# EVO_Schematic.net
KiCad netlist of a schematic drawn in Altium Designer
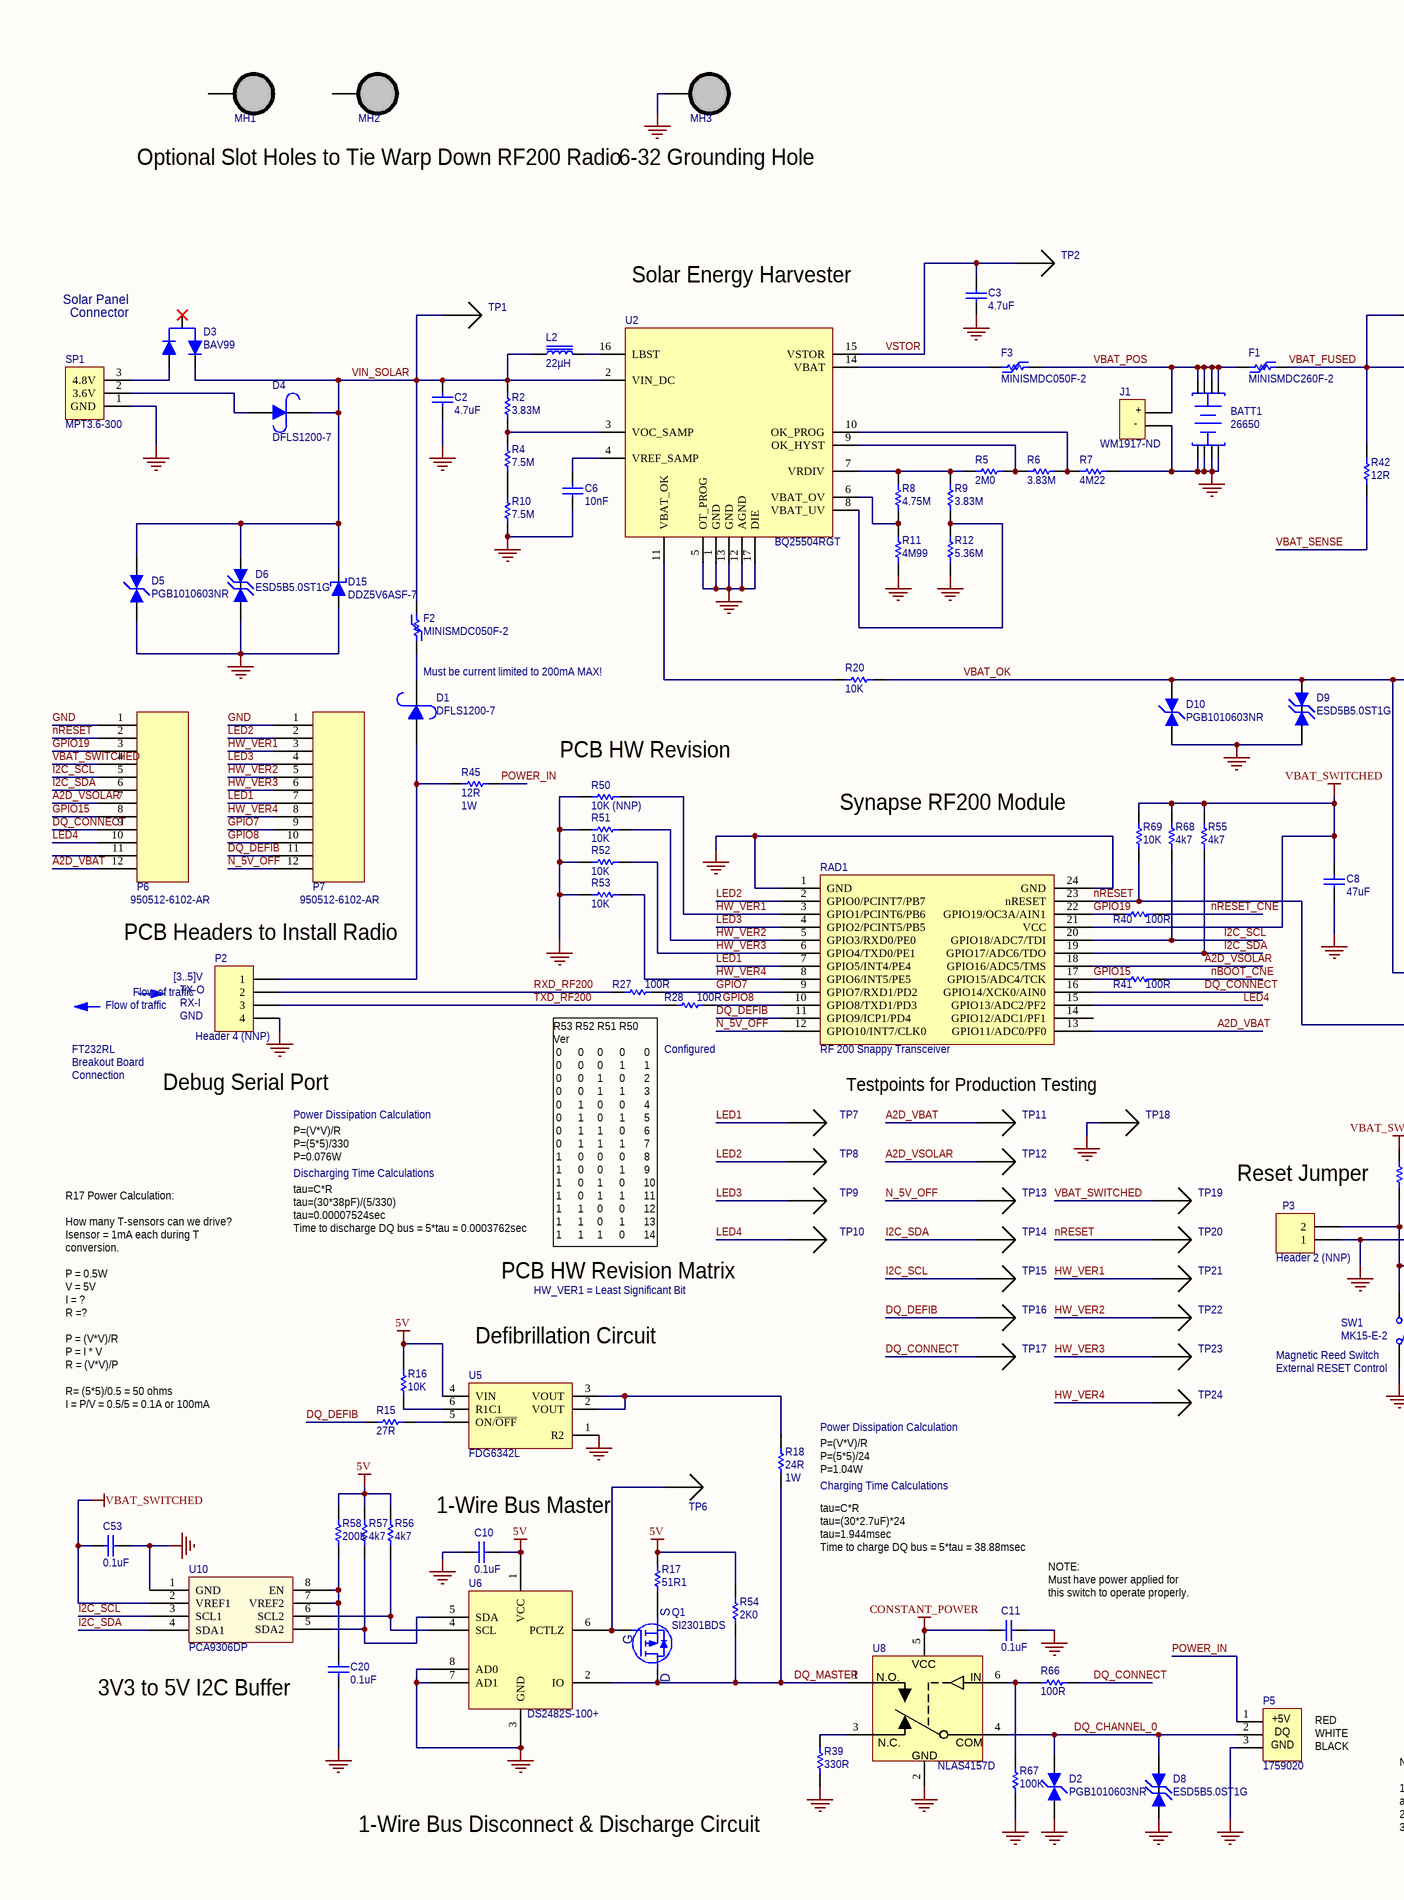
[diagram p0: EVO Schematic.SchDoc, left]
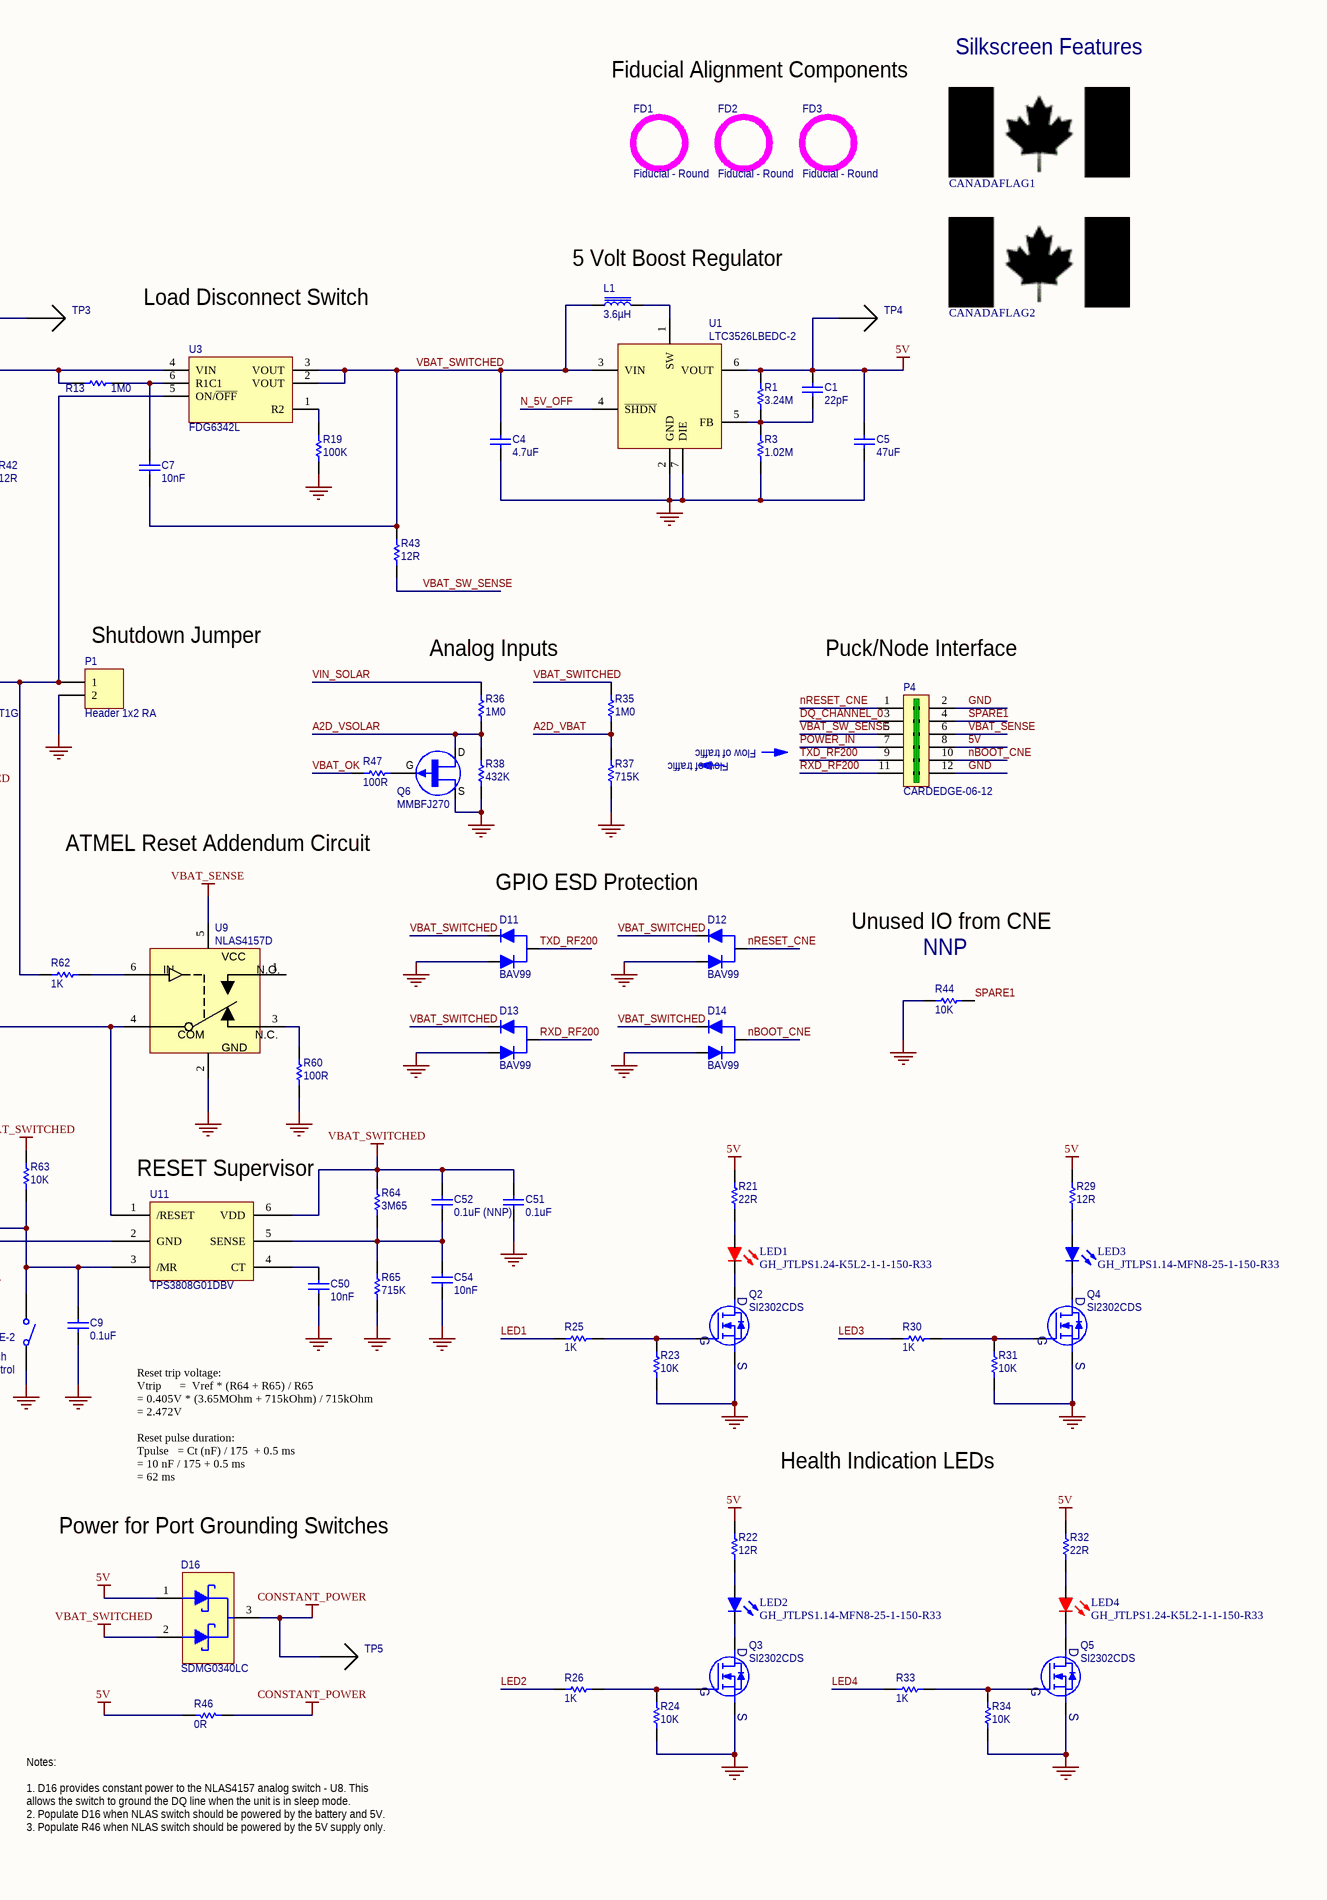
[diagram p1: EVO Schematic.SchDoc, right]

(export (version "E")
  (design (tool "Eeschema 10.0.6"))
  (components
    (comp (ref "BATT1")
      (value "26650")
      (footprint "Battery_26650")
      (description "26650 LiFePO4 3.2V 3300mAh")
      (fields
        (field (name "MANUFACTURER") "TACBattery")
        (field (name "MANUFACTURER PART NUMBER") "26650 3.2V 1500mAh with wire")
      )
      (libsource (lib "Swage") (part "BATT_18650_1"))
    )
    (comp (ref "C1")
      (value "22pF")
      (footprint "RC0805")
      (description "CAP CER 22PF 50V 5% NPO 0805")
      (fields
        (field (name "MANUFACTURER") "Yageo")
        (field (name "MANUFACTURER PART NUMBER") "CC0805JRNPO9BN220")
      )
      (libsource (lib "Swage") (part "CC0805JRNPO9BN220"))
    )
    (comp (ref "C2")
      (value "4.7uF")
      (footprint "RC0805")
      (description "CAP CER 4.7UF 6.3V 10% X5R 0805")
      (fields
        (field (name "MANUFACTURER") "Taiyo Yuden")
        (field (name "MANUFACTURER PART NUMBER") "JMK212BJ475KG-T")
      )
      (libsource (lib "Swage") (part "JMK212BJ475KG-T"))
    )
    (comp (ref "C3")
      (value "4.7uF")
      (footprint "RC0805")
      (description "CAP CER 4.7UF 6.3V 10% X5R 0805")
      (fields
        (field (name "MANUFACTURER") "Taiyo Yuden")
        (field (name "MANUFACTURER PART NUMBER") "JMK212BJ475KG-T")
      )
      (libsource (lib "Swage") (part "JMK212BJ475KG-T"))
    )
    (comp (ref "C4")
      (value "4.7uF")
      (footprint "RC0805")
      (description "CAP CER 4.7UF 6.3V 10% X5R 0805")
      (fields
        (field (name "MANUFACTURER") "Taiyo Yuden")
        (field (name "MANUFACTURER PART NUMBER") "JMK212BJ475KG-T")
      )
      (libsource (lib "Swage") (part "JMK212BJ475KG-T"))
    )
    (comp (ref "C5")
      (value "47uF")
      (footprint "RC1206")
      (description "CAP CER 47UF 10V 20% X5R 1206")
      (fields
        (field (name "MANUFACTURER") "Taiyo Yuden")
        (field (name "MANUFACTURER PART NUMBER") "LMK316BJ476ML-T")
      )
      (libsource (lib "Swage") (part "LMK316BJ476ML-T"))
    )
    (comp (ref "C6")
      (value "10nF")
      (footprint "RC0805")
      (description "CAP CER 10000PF 100V X7R 0805")
      (fields
        (field (name "MANUFACTURER") "TDK Corporation")
        (field (name "MANUFACTURER PART NUMBER") "C2012X7R2A103K")
      )
      (libsource (lib "Swage") (part "C2012X7R2A103K"))
    )
    (comp (ref "C7")
      (value "10nF")
      (footprint "RC0603")
      (description "CAP CER 10000PF 50V 10% X7R 0603")
      (fields
        (field (name "MANUFACTURER") "TDK Corporation")
        (field (name "MANUFACTURER PART NUMBER") "C1608X7R1H103K")
      )
      (libsource (lib "Swage") (part "C1608X7R1H103K"))
    )
    (comp (ref "C8")
      (value "47uF")
      (footprint "RC1206")
      (description "CAP CER 47UF 10V 20% X5R 1206")
      (fields
        (field (name "MANUFACTURER") "Taiyo Yuden")
        (field (name "MANUFACTURER PART NUMBER") "LMK316BJ476ML-T")
      )
      (libsource (lib "Swage") (part "LMK316BJ476ML-T"))
    )
    (comp (ref "C9")
      (value "0.1uF")
      (footprint "RC0603")
      (description "CAP CERM .1UF 10% 16V X7R 0603")
      (fields
        (field (name "MANUFACTURER") "AVX Corporation")
        (field (name "MANUFACTURER PART NUMBER") "0603YC104KAT2A")
      )
      (libsource (lib "Swage") (part "0603YC104KAT2A"))
    )
    (comp (ref "C10")
      (value "0.1uF")
      (footprint "RC0603")
      (description "CAP CERM .1UF 10% 16V X7R 0603")
      (fields (field (name "TOLERANCE") "±10%") (field (name "MANUFACTURER PART NUMBER") "0603YC104KAT2A"))
      (libsource (lib "Swage") (part "0603YC104KAT2A"))
    )
    (comp (ref "C11")
      (value "0.1uF")
      (footprint "RC0603")
      (description "CAP CERM .1UF 10% 16V X7R 0603")
      (fields (field (name "TOLERANCE") "±10%") (field (name "MANUFACTURER PART NUMBER") "0603YC104KAT2A"))
      (libsource (lib "Swage") (part "0603YC104KAT2A"))
    )
    (comp (ref "C20")
      (value "0.1uF")
      (footprint "RC0603")
      (description "CAP CERM .1UF 10% 16V X7R 0603")
      (fields (field (name "TOLERANCE") "±10%") (field (name "MANUFACTURER PART NUMBER") "0603YC104KAT2A"))
      (libsource (lib "Swage") (part "0603YC104KAT2A"))
    )
    (comp (ref "C50")
      (value "10nF")
      (footprint "RC0603")
      (description "CAP CER 10000PF 50V 10% X7R 0603")
      (fields (field (name "TOLERANCE") "±10%") (field (name "MANUFACTURER") "TDK Corporation"))
      (libsource (lib "Swage") (part "C1608X7R1H103K"))
    )
    (comp (ref "C51")
      (value "0.1uF")
      (footprint "RC0603")
      (description "CAP CERM .1UF 10% 16V X7R 0603")
      (fields (field (name "TOLERANCE") "±10%") (field (name "MANUFACTURER PART NUMBER") "0603YC104KAT2A"))
      (libsource (lib "Swage") (part "0603YC104KAT2A"))
    )
    (comp (ref "C52")
      (value "0.1uF (NNP)")
      (footprint "RC0603")
      (description "CAP CERM .1UF 10% 16V X7R 0603")
      (fields (field (name "TOLERANCE") "±10%") (field (name "MANUFACTURER PART NUMBER") "0603YC104KAT2A"))
      (libsource (lib "Swage") (part "0603YC104KAT2A"))
    )
    (comp (ref "C53")
      (value "0.1uF")
      (footprint "RC0603")
      (description "CAP CERM .1UF 10% 16V X7R 0603")
      (fields (field (name "TOLERANCE") "±10%") (field (name "MANUFACTURER PART NUMBER") "0603YC104KAT2A"))
      (libsource (lib "Swage") (part "0603YC104KAT2A"))
    )
    (comp (ref "C54")
      (value "10nF")
      (footprint "RC0603")
      (description "CAP CER 10000PF 50V 10% X7R 0603")
      (fields (field (name "TOLERANCE") "±10%") (field (name "MANUFACTURER") "TDK Corporation"))
      (libsource (lib "Swage") (part "C1608X7R1H103K"))
    )
    (comp (ref "CANADAFLAG1")
      (value "Canada Flag")
      (footprint "CanadaFlag500x250")
      (libsource (lib "Swage") (part "CanadaFlag"))
    )
    (comp (ref "CANADAFLAG2")
      (value "Canada Flag")
      (footprint "CanadaFlag500x250")
      (libsource (lib "Swage") (part "CanadaFlag"))
    )
    (comp (ref "D1")
      (value "DFLS1200-7")
      (footprint "POWERDI-123")
      (description "DIODE SCHOTTKY 1A 200V PWRDI 123")
      (fields (field (name "MANUFACTURER") "Diodes Inc"))
      (libsource (lib "Swage") (part "DFLS1200-7"))
    )
    (comp (ref "D2")
      (value "PGB1010603NR")
      (footprint "RC0603")
      (description "SUPPRESSOR ESD 24VDC 0603 SMD")
      (fields (field (name "MANUFACTURER") "Littelfuse Inc"))
      (libsource (lib "Swage") (part "PGB1010603NR"))
    )
    (comp (ref "D3")
      (value "BAV99")
      (footprint "SOT23")
      (description "DIODE SW DUAL 75V 350MW SOT23-3")
      (fields
        (field (name "MANUFACTURER") "Diodes Inc")
        (field (name "MANUFACTURER PART NUMBER") "BAV99-7-F")
      )
      (libsource (lib "Swage") (part "BAV99-7-F"))
    )
    (comp (ref "D4")
      (value "DFLS1200-7")
      (footprint "POWERDI-123")
      (description "DIODE SCHOTTKY 1A 200V PWRDI 123")
      (fields (field (name "MANUFACTURER") "Diodes Inc"))
      (libsource (lib "Swage") (part "DFLS1200-7"))
    )
    (comp (ref "D5")
      (value "PGB1010603NR")
      (footprint "RC0603")
      (description "SUPPRESSOR ESD 24VDC 0603 SMD")
      (fields (field (name "MANUFACTURER") "Littelfuse Inc"))
      (libsource (lib "Swage") (part "PGB1010603NR"))
    )
    (comp (ref "D6")
      (value "ESD5B5.0ST1G")
      (footprint "SOD-523")
      (description "TVS BIDIRECT 50W SOD523")
      (fields (field (name "MANUFACTURER") "ON Semiconductor"))
      (libsource (lib "Swage") (part "ESD5B5.0ST1G"))
    )
    (comp (ref "D8")
      (value "ESD5B5.0ST1G")
      (footprint "SOD-523")
      (description "TVS BIDIRECT 50W SOD523")
      (fields (field (name "MANUFACTURER") "ON Semiconductor"))
      (libsource (lib "Swage") (part "ESD5B5.0ST1G"))
    )
    (comp (ref "D9")
      (value "ESD5B5.0ST1G")
      (footprint "SOD-523")
      (description "TVS BIDIRECT 50W SOD523")
      (fields (field (name "MANUFACTURER") "ON Semiconductor"))
      (libsource (lib "Swage") (part "ESD5B5.0ST1G"))
    )
    (comp (ref "D10")
      (value "PGB1010603NR")
      (footprint "RC0603")
      (description "SUPPRESSOR ESD 24VDC 0603 SMD")
      (fields (field (name "MANUFACTURER") "Littelfuse Inc"))
      (libsource (lib "Swage") (part "PGB1010603NR"))
    )
    (comp (ref "D11")
      (value "BAV99")
      (footprint "SOT23")
      (description "DIODE SW DUAL 75V 350MW SOT23-3")
      (fields
        (field (name "MANUFACTURER") "Diodes Inc")
        (field (name "MANUFACTURER PART NUMBER") "BAV99-7-F")
      )
      (libsource (lib "Swage") (part "BAV99-7-F"))
    )
    (comp (ref "D12")
      (value "BAV99")
      (footprint "SOT23")
      (description "DIODE SW DUAL 75V 350MW SOT23-3")
      (fields
        (field (name "MANUFACTURER") "Diodes Inc")
        (field (name "MANUFACTURER PART NUMBER") "BAV99-7-F")
      )
      (libsource (lib "Swage") (part "BAV99-7-F"))
    )
    (comp (ref "D13")
      (value "BAV99")
      (footprint "SOT23")
      (description "DIODE SW DUAL 75V 350MW SOT23-3")
      (fields
        (field (name "MANUFACTURER") "Diodes Inc")
        (field (name "MANUFACTURER PART NUMBER") "BAV99-7-F")
      )
      (libsource (lib "Swage") (part "BAV99-7-F"))
    )
    (comp (ref "D14")
      (value "BAV99")
      (footprint "SOT23")
      (description "DIODE SW DUAL 75V 350MW SOT23-3")
      (fields
        (field (name "MANUFACTURER") "Diodes Inc")
        (field (name "MANUFACTURER PART NUMBER") "BAV99-7-F")
      )
      (libsource (lib "Swage") (part "BAV99-7-F"))
    )
    (comp (ref "D15")
      (value "DDZ5V6ASF-7")
      (footprint "SOD323F")
      (description "DIODE ZENER 5.42V 500MW SOD323F")
      (fields (field (name "MANUFACTURER") "Diodes Inc") (field (name "TOLERANCE") "±2%"))
      (libsource (lib "Swage") (part "DDZ5V6ASF-7"))
    )
    (comp (ref "D16")
      (value "SDMG0340LC")
      (footprint "SOT-323")
      (description "DIODE SCHOTTKY 40V 30MA SOT323")
      (fields
        (field (name "MANUFACTURER") "Diodes Inc")
        (field (name "MANUFACTURER PART NUMBER") "SDMG0340LC-7-F")
      )
      (libsource (lib "Swage") (part "SDMG0340LC-7-F"))
    )
    (comp (ref "F1")
      (value "MINISMDC260F-2")
      (footprint "MINISMDC260F")
      (description "POLYSWITCH 2.6A RESET FUSE SMD")
      (fields (field (name "MANUFACTURER") "TE Connectivity"))
      (libsource (lib "Swage") (part "MINISMDC260F-2"))
    )
    (comp (ref "F2")
      (value "MINISMDC050F-2")
      (footprint "MINISMD050")
      (description "POLYSWITCH .50A RESET FUSE SMD")
      (fields (field (name "MANUFACTURER") "TE Connectivity"))
      (libsource (lib "Swage") (part "MINISMDC050F-2"))
    )
    (comp (ref "F3")
      (value "MINISMDC050F-2")
      (footprint "MINISMD050")
      (description "POLYSWITCH .50A RESET FUSE SMD")
      (fields (field (name "MANUFACTURER") "TE Connectivity"))
      (libsource (lib "Swage") (part "MINISMDC050F-2"))
    )
    (comp (ref "FD1")
      (value "Fiducial - Round")
      (footprint "FIDUCIAL ROUND SMALL")
      (description "Fiducial Round")
      (libsource (lib "StormaxV13") (part "Fiducial"))
    )
    (comp (ref "FD2")
      (value "Fiducial - Round")
      (footprint "FIDUCIAL ROUND SMALL")
      (description "Fiducial Round")
      (libsource (lib "StormaxV13") (part "Fiducial"))
    )
    (comp (ref "FD3")
      (value "Fiducial - Round")
      (footprint "FIDUCIAL ROUND SMALL")
      (description "Fiducial Round")
      (libsource (lib "StormaxV13") (part "Fiducial"))
    )
    (comp (ref "J1")
      (value "CONN")
      (footprint "BATTERYCONNECTOR")
      (description "CONN HEADER 2POS 3MM VERT GOLD")
      (fields
        (field (name "MANUFACTURER") "Molex Inc")
        (field (name "MANUFACTURER PART NUMBER") "436500216")
        (field (name "SUPPLIER PART NUMBER 1") "WM1917-ND")
      )
      (libsource (lib "Swage") (part "436500216"))
    )
    (comp (ref "L1")
      (value "3.6µH")
      (footprint "IND-WURTH")
      (description "INDUCTOR POWER 3.6UH 1.38A SMD")
      (fields
        (field (name "MANUFACTURER") "Wurth Electronics Inc")
        (field (name "MANUFACTURER PART NUMBER") "744031003")
      )
      (libsource (lib "Swage") (part "744031003"))
    )
    (comp (ref "L2")
      (value "22µH")
      (footprint "IND-SRR0604")
      (description "INDUCTOR PWR 22UH 20% SHIELD SMD")
      (fields
        (field (name "MANUFACTURER") "Bourns Inc.")
        (field (name "MANUFACTURER PART NUMBER") "SRR0604-220ML")
      )
      (libsource (lib "Swage") (part "SRR0604-220ML"))
    )
    (comp (ref "LED1")
      (value "GH_JTLPS1.24-K5L2-1-1-150-R33")
      (footprint "GHJTLPS124K5L211150R33")
      (description "LED")
      (fields (field (name "MANUFACTURER_PART_NUMBER") "GH JTLPS1.24-K5L2-1-1-150-R33"))
      (libsource (lib "Swage") (part "GH_JTLPS1.24-K5L2-1-1-150-R33"))
    )
    (comp (ref "LED2")
      (value "GH_JTLPS1.14-MFN8-25-1-150-R33")
      (footprint "GHJTLPS124K5L211150R33")
      (description "LED")
      (fields (field (name "MANUFACTURER_PART_NUMBER") "GH JTLPS1.24-K5L2-1-1-150-R33"))
      (libsource (lib "Swage") (part "GH_JTLPS1.14-MFN8-25-1-150-R33"))
    )
    (comp (ref "LED3")
      (value "GH_JTLPS1.14-MFN8-25-1-150-R33")
      (footprint "GHJTLPS124K5L211150R33")
      (description "LED")
      (fields (field (name "MANUFACTURER_PART_NUMBER") "GH JTLPS1.24-K5L2-1-1-150-R33"))
      (libsource (lib "Swage") (part "GH_JTLPS1.14-MFN8-25-1-150-R33"))
    )
    (comp (ref "LED4")
      (value "GH_JTLPS1.24-K5L2-1-1-150-R33")
      (footprint "GHJTLPS124K5L211150R33")
      (description "LED")
      (fields (field (name "MANUFACTURER_PART_NUMBER") "GH JTLPS1.24-K5L2-1-1-150-R33"))
      (libsource (lib "Swage") (part "GH_JTLPS1.24-K5L2-1-1-150-R33"))
    )
    (comp (ref "MH1")
      (value "MountingHole")
      (footprint "MountingHole")
      (description "PCB Mounting Hole, 0.150\" hole, 0.270\" Keepout")
      (libsource (lib "Swage") (part "MountingHole"))
    )
    (comp (ref "MH2")
      (value "MountingHole")
      (footprint "MountingHole")
      (description "PCB Mounting Hole, 0.150\" hole, 0.270\" Keepout")
      (libsource (lib "Swage") (part "MountingHole"))
    )
    (comp (ref "MH3")
      (value "MountingHole")
      (footprint "MountingHole")
      (description "PCB Mounting Hole, 0.150\" hole, 0.270\" Keepout")
      (libsource (lib "Swage") (part "MountingHole"))
    )
    (comp (ref "P1")
      (value "Header 1x2 RA")
      (footprint "HDR1X2")
      (description "SIL HORIZ PC TAIL PIN HEADER")
      (fields
        (field (name "MANUFACTURER") "Harwin Inc")
        (field (name "MANUFACTURER PART NUMBER") "M20-9960245")
      )
      (libsource (lib "Swage") (part "M20-9960245"))
    )
    (comp (ref "P2")
      (value "Header 4 (NNP)")
      (footprint "HDR1X4")
      (description "Header, 4-Pin")
      (fields
        (field (name "MANUFACTURER") "3M")
        (field (name "MANUFACTURER PART NUMBER") "2340-6111TG")
        (field (name "PUBLISHER") "Altium Limited")
      )
      (libsource (lib "Swage") (part "Header 4"))
    )
    (comp (ref "P3")
      (value "Header 2 (NNP)")
      (footprint "HDR1X2")
      (description "Header, 2-Pin")
      (fields
        (field (name "MANUFACTURER") "3M")
        (field (name "MANUFACTURER PART NUMBER") "2340-6111TG")
        (field (name "PUBLISHER") "Altium Limited")
      )
      (libsource (lib "Miscellaneous Connectors") (part "Header 2"))
    )
    (comp (ref "P4")
      (value "CARDEDGE-06-12")
      (footprint "EdgeConnectorFingers")
      (description "CONN EDGECARD 6POS .100 FINGERS")
      (libsource (lib "Swage") (part "CARDEDGE-06-12"))
    )
    (comp (ref "P5")
      (value "1759020")
      (footprint "PC-1759020")
      (description "CONN HEADER RT ANG 3POS 5.08MM")
      (fields (field (name "MANUFACTURER") "Phoenix Contact") (field (name "VOLTAGE") "300V"))
      (libsource (lib "Swage") (part "1759020"))
    )
    (comp (ref "P6")
      (value "3M-950512-6102-AR")
      (footprint "HEADER1X12-2MM")
      (description "CONN SOCKET 12POS 2MM VERT T/H")
      (fields (field (name "MANUFACTURER") "3M") (field (name "MANUFACTURER PART NUMBER") "950512-6102-AR"))
      (libsource (lib "Swage") (part "3M-950512-6102-AR"))
    )
    (comp (ref "P7")
      (value "3M-950512-6102-AR")
      (footprint "HEADER1X12-2MM")
      (description "CONN SOCKET 12POS 2MM VERT T/H")
      (fields (field (name "MANUFACTURER") "3M") (field (name "MANUFACTURER PART NUMBER") "950512-6102-AR"))
      (libsource (lib "Swage") (part "3M-950512-6102-AR"))
    )
    (comp (ref "Q1")
      (value "SI2301BDS")
      (footprint "SOT23(DGS)")
      (description "MOSFET P-CH 20V 2.2A SOT23-3")
      (fields
        (field (name "MANUFACTURER") "Vishay/Siliconix")
        (field (name "MANUFACTURER PART NUMBER") "SI2301BDS-T1-E3")
      )
      (libsource (lib "Swage") (part "SI2301BDS-T1-E3"))
    )
    (comp (ref "Q2")
      (value "SI2302CDS")
      (footprint "SOT23")
      (description "MOSFET N-CH 20V 2.6A SOT23-3")
      (fields
        (field (name "MANUFACTURER") "Vishay Siliconix")
        (field (name "MANUFACTURER PART NUMBER") "SI2302CDS-T1-GE3")
      )
      (libsource (lib "Swage") (part "SI2302CDS-T1-GE3"))
    )
    (comp (ref "Q3")
      (value "SI2302CDS")
      (footprint "SOT23")
      (description "MOSFET N-CH 20V 2.6A SOT23-3")
      (fields
        (field (name "MANUFACTURER") "Vishay Siliconix")
        (field (name "MANUFACTURER PART NUMBER") "SI2302CDS-T1-GE3")
      )
      (libsource (lib "Swage") (part "SI2302CDS-T1-GE3"))
    )
    (comp (ref "Q4")
      (value "SI2302CDS")
      (footprint "SOT23")
      (description "MOSFET N-CH 20V 2.6A SOT23-3")
      (fields
        (field (name "MANUFACTURER") "Vishay Siliconix")
        (field (name "MANUFACTURER PART NUMBER") "SI2302CDS-T1-GE3")
      )
      (libsource (lib "Swage") (part "SI2302CDS-T1-GE3"))
    )
    (comp (ref "Q5")
      (value "SI2302CDS")
      (footprint "SOT23")
      (description "MOSFET N-CH 20V 2.6A SOT23-3")
      (fields
        (field (name "MANUFACTURER") "Vishay Siliconix")
        (field (name "MANUFACTURER PART NUMBER") "SI2302CDS-T1-GE3")
      )
      (libsource (lib "Swage") (part "SI2302CDS-T1-GE3"))
    )
    (comp (ref "Q6")
      (value "MMBFJ270")
      (footprint "SOT23")
      (description "IC SWITCH P-CHANNEL SOT-23")
      (fields (field (name "MANUFACTURER") "Fairchild Semiconductor"))
      (libsource (lib "Swage") (part "MMBFJ270"))
    )
    (comp (ref "R1")
      (value "3.24M")
      (footprint "RC0805")
      (description "RES 3.24M OHM 1/8W 1% 0805 SMD")
      (fields
        (field (name "MANUFACTURER") "Vishay Dale")
        (field (name "MANUFACTURER PART NUMBER") "CRCW08053M24FKEA")
      )
      (libsource (lib "Swage") (part "CRCW08053M24FKEA"))
    )
    (comp (ref "R2")
      (value "3.83M")
      (footprint "RC0603")
      (description "RES 3.83M OHM 1/10W 1% 0603 SMD")
      (fields
        (field (name "MANUFACTURER") "Vishay Dale")
        (field (name "MANUFACTURER PART NUMBER") "CRCW06033M83FKEA")
      )
      (libsource (lib "Swage") (part "CRCW06033M83FKEA"))
    )
    (comp (ref "R3")
      (value "1.02M")
      (footprint "RC0805")
      (description "RES 1.02M OHM 1/8W 1% 0805 SMD")
      (fields
        (field (name "MANUFACTURER") "Vishay Dale")
        (field (name "MANUFACTURER PART NUMBER") "CRCW08051M02FKEA")
      )
      (libsource (lib "Swage") (part "CRCW08051M02FKEA"))
    )
    (comp (ref "R4")
      (value "7.5M")
      (footprint "RC0603")
      (description "RES 7.50M OHM 1/10W 1% 0603 SMD")
      (fields
        (field (name "MANUFACTURER") "Vishay Dale")
        (field (name "MANUFACTURER PART NUMBER") "CRCW06037M50FKEA")
      )
      (libsource (lib "Swage") (part "CRCW06037M50FKEA"))
    )
    (comp (ref "R5")
      (value "2M0")
      (footprint "RC0603")
      (description "RES 2.00M OHM 1/10W 1% 0603 SMD")
      (fields
        (field (name "MANUFACTURER") "Vishay Dale")
        (field (name "MANUFACTURER PART NUMBER") "CRCW06032M00FKEA")
      )
      (libsource (lib "Swage") (part "CRCW06032M00FKEA"))
    )
    (comp (ref "R6")
      (value "3.83M")
      (footprint "RC0603")
      (description "RES 3.83M OHM 1/10W 1% 0603 SMD")
      (fields
        (field (name "MANUFACTURER") "Vishay Dale")
        (field (name "MANUFACTURER PART NUMBER") "CRCW06033M83FKEA")
      )
      (libsource (lib "Swage") (part "CRCW06033M83FKEA"))
    )
    (comp (ref "R7")
      (value "4M22")
      (footprint "RC0603")
      (description "RES 4.22M OHM 1/10W 1% 0603 SMD")
      (fields
        (field (name "MANUFACTURER") "Vishay Dale")
        (field (name "MANUFACTURER PART NUMBER") "CRCW06034M22FKEA")
      )
      (libsource (lib "Swage") (part "CRCW06034M22FKEA"))
    )
    (comp (ref "R8")
      (value "4.75M")
      (footprint "rc0603")
      (description "RES 4.75M OHM 1/10W 1% 0603 SMD")
      (fields
        (field (name "MANUFACTURER") "Vishay Dale")
        (field (name "MANUFACTURER PART NUMBER") "CRCW06034M75FKEA")
      )
      (libsource (lib "Swage") (part "CRCW06034M75FKEA"))
    )
    (comp (ref "R9")
      (value "3.83M")
      (footprint "RC0603")
      (description "RES 3.83M OHM 1/10W 1% 0603 SMD")
      (fields
        (field (name "MANUFACTURER") "Vishay Dale")
        (field (name "MANUFACTURER PART NUMBER") "CRCW06033M83FKEA")
      )
      (libsource (lib "Swage") (part "CRCW06033M83FKEA"))
    )
    (comp (ref "R10")
      (value "7.5M")
      (footprint "RC0603")
      (description "RES 7.50M OHM 1/10W 1% 0603 SMD")
      (fields
        (field (name "MANUFACTURER") "Vishay Dale")
        (field (name "MANUFACTURER PART NUMBER") "CRCW06037M50FKEA")
      )
      (libsource (lib "Swage") (part "CRCW06037M50FKEA"))
    )
    (comp (ref "R11")
      (value "4M99")
      (footprint "rc0603")
      (description "RES 4.99M OHM 1/10W 1% 0603 SMD")
      (fields
        (field (name "MANUFACTURER") "Vishay Dale")
        (field (name "MANUFACTURER PART NUMBER") "CRCW06034M99FKEA")
      )
      (libsource (lib "Swage") (part "CRCW06034M99FKEA"))
    )
    (comp (ref "R12")
      (value "5.36M")
      (footprint "RC0603")
      (description "RES 5.36M OHM 1/10W 1% 0603 SMD")
      (fields
        (field (name "MANUFACTURER") "Vishay Dale")
        (field (name "MANUFACTURER PART NUMBER") "CRCW06035M36FKEA")
      )
      (libsource (lib "Swage") (part "CRCW06035M36FKEA (2)"))
    )
    (comp (ref "R13")
      (value "1M0")
      (footprint "RESC1608X06N")
      (description "RES 1.0M OHM 1/10W 5% 0603 SMD")
      (fields (field (name "TOLERANCE") "±5%") (field (name "MANUFACTURER") "Panasonic - ECG"))
      (libsource (lib "Swage") (part "ERJ-3GEYJ105V"))
    )
    (comp (ref "R15")
      (value "27R")
      (footprint "RC0603")
      (description "RES 27.0 OHM 1/10W 1% 0603 SMD")
      (fields
        (field (name "MANUFACTURER") "Panasonic Electronic Components")
        (field (name "MANUFACTURER PART NUMBER") "ERJ-3EKF27R0V")
      )
      (libsource (lib "Swage") (part "ERJ-3EKF27R0V"))
    )
    (comp (ref "R16")
      (value "10K")
      (footprint "RC0603")
      (description "RES 10K OHM 1/10W 5% 0603 SMD")
      (fields
        (field (name "MANUFACTURER") "Panasonic Electronic Components")
        (field (name "MANUFACTURER PART NUMBER") "ERJ-3GEYJ103V")
      )
      (libsource (lib "Swage") (part "ERJ-3GEYJ103V"))
    )
    (comp (ref "R17")
      (value "51R1")
      (footprint "RC3225X07N")
      (description "RES 51.1 OHM 1/2W 1% 1210 SMD")
      (fields
        (field (name "MANUFACTURER") "Panasonic Electronic Components")
        (field (name "MANUFACTURER PART NUMBER") "ERJ-14NF51R1U")
      )
      (libsource (lib "Swage") (part "ERJ-14NF51R1U"))
    )
    (comp (ref "R18")
      (value "24R")
      (footprint "RES2512")
      (description "RES 24 OHM 1W 5% 2512 SMD")
      (fields
        (field (name "MANUFACTURER") "TTI Inc.")
        (field (name "MANUFACTURER PART NUMBER") "CRCW251224R0JNEG")
        (field (name "POWER (WATTS)") "1W")
      )
      (libsource (lib "Swage") (part "RMCF2512JT24R0"))
    )
    (comp (ref "R19")
      (value "100K")
      (footprint "RC0603")
      (description "RES 100K OHM 1/10W 5% 0603 SMD")
      (fields
        (field (name "MANUFACTURER") "Panasonic Electronic Components")
        (field (name "MANUFACTURER PART NUMBER") "ERJ-3GEYJ104V")
      )
      (libsource (lib "Swage") (part "ERJ-3GEYJ104V"))
    )
    (comp (ref "R20")
      (value "10K")
      (footprint "RC0603")
      (description "RES 10K OHM 1/10W 5% 0603 SMD")
      (fields
        (field (name "MANUFACTURER") "Panasonic Electronic Components")
        (field (name "MANUFACTURER PART NUMBER") "ERJ-3GEYJ103V")
      )
      (libsource (lib "Swage") (part "ERJ-3GEYJ103V"))
    )
    (comp (ref "R21")
      (value "22R")
      (footprint "RC1206")
      (description "RES 22.0 OHM 1/4W 1% 1206 SMD")
      (fields
        (field (name "MANUFACTURER") "Yageo")
        (field (name "MANUFACTURER PART NUMBER") "RC1206FR-0722RL")
      )
      (libsource (lib "Swage") (part "RC1206FR-0722RL"))
    )
    (comp (ref "R22")
      (value "12R")
      (footprint "RC1206")
      (description "RES 12.0 OHM 1/4W 1% 1206 SMD")
      (fields
        (field (name "MANUFACTURER") "Yageo")
        (field (name "MANUFACTURER PART NUMBER") "RC1206FR-0712RL")
      )
      (libsource (lib "Swage") (part "RC1206FR-0712RL"))
    )
    (comp (ref "R23")
      (value "10K")
      (footprint "RC0603")
      (description "RES 10K OHM 1/10W 5% 0603 SMD")
      (fields
        (field (name "MANUFACTURER") "Panasonic Electronic Components")
        (field (name "MANUFACTURER PART NUMBER") "ERJ-3GEYJ103V")
      )
      (libsource (lib "Swage") (part "ERJ-3GEYJ103V"))
    )
    (comp (ref "R24")
      (value "10K")
      (footprint "RC0603")
      (description "RES 10K OHM 1/10W 5% 0603 SMD")
      (fields
        (field (name "MANUFACTURER") "Panasonic Electronic Components")
        (field (name "MANUFACTURER PART NUMBER") "ERJ-3GEYJ103V")
      )
      (libsource (lib "Swage") (part "ERJ-3GEYJ103V"))
    )
    (comp (ref "R25")
      (value "1K")
      (footprint "rc0603")
      (description "RES 1.0K OHM 1/10W 5% 0603 SMD")
      (fields
        (field (name "MANUFACTURER") "Panasonic Electronic Components")
        (field (name "MANUFACTURER PART NUMBER") "ERJ-3GEYJ102V")
      )
      (libsource (lib "Swage") (part "ERJ-3GEYJ102V"))
    )
    (comp (ref "R26")
      (value "1K")
      (footprint "rc0603")
      (description "RES 1.0K OHM 1/10W 5% 0603 SMD")
      (fields
        (field (name "MANUFACTURER") "Panasonic Electronic Components")
        (field (name "MANUFACTURER PART NUMBER") "ERJ-3GEYJ102V")
      )
      (libsource (lib "Swage") (part "ERJ-3GEYJ102V"))
    )
    (comp (ref "R27")
      (value "100R")
      (footprint "RC0603")
      (description "RES 100 OHM 1/10W 5% 0603 SMD")
      (fields
        (field (name "TOLERANCE") "±5%")
        (field (name "MANUFACTURER") "Panasonic Electronic Components")
      )
      (libsource (lib "Swage") (part "ERJ-3GEYJ101V"))
    )
    (comp (ref "R28")
      (value "100R")
      (footprint "RC0603")
      (description "RES 100 OHM 1/10W 5% 0603 SMD")
      (fields
        (field (name "TOLERANCE") "±5%")
        (field (name "MANUFACTURER") "Panasonic Electronic Components")
      )
      (libsource (lib "Swage") (part "ERJ-3GEYJ101V"))
    )
    (comp (ref "R29")
      (value "12R")
      (footprint "RC1206")
      (description "RES 12.0 OHM 1/4W 1% 1206 SMD")
      (fields
        (field (name "MANUFACTURER") "Yageo")
        (field (name "MANUFACTURER PART NUMBER") "RC1206FR-0712RL")
      )
      (libsource (lib "Swage") (part "RC1206FR-0712RL"))
    )
    (comp (ref "R30")
      (value "1K")
      (footprint "rc0603")
      (description "RES 1.0K OHM 1/10W 5% 0603 SMD")
      (fields
        (field (name "MANUFACTURER") "Panasonic Electronic Components")
        (field (name "MANUFACTURER PART NUMBER") "ERJ-3GEYJ102V")
      )
      (libsource (lib "Swage") (part "ERJ-3GEYJ102V"))
    )
    (comp (ref "R31")
      (value "10K")
      (footprint "RC0603")
      (description "RES 10K OHM 1/10W 5% 0603 SMD")
      (fields
        (field (name "MANUFACTURER") "Panasonic Electronic Components")
        (field (name "MANUFACTURER PART NUMBER") "ERJ-3GEYJ103V")
      )
      (libsource (lib "Swage") (part "ERJ-3GEYJ103V"))
    )
    (comp (ref "R32")
      (value "22R")
      (footprint "RC1206")
      (description "RES 22.0 OHM 1/4W 1% 1206 SMD")
      (fields
        (field (name "MANUFACTURER") "Yageo")
        (field (name "MANUFACTURER PART NUMBER") "RC1206FR-0722RL")
      )
      (libsource (lib "Swage") (part "RC1206FR-0722RL"))
    )
    (comp (ref "R33")
      (value "1K")
      (footprint "rc0603")
      (description "RES 1.0K OHM 1/10W 5% 0603 SMD")
      (fields
        (field (name "MANUFACTURER") "Panasonic Electronic Components")
        (field (name "MANUFACTURER PART NUMBER") "ERJ-3GEYJ102V")
      )
      (libsource (lib "Swage") (part "ERJ-3GEYJ102V"))
    )
    (comp (ref "R34")
      (value "10K")
      (footprint "RC0603")
      (description "RES 10K OHM 1/10W 5% 0603 SMD")
      (fields
        (field (name "MANUFACTURER") "Panasonic Electronic Components")
        (field (name "MANUFACTURER PART NUMBER") "ERJ-3GEYJ103V")
      )
      (libsource (lib "Swage") (part "ERJ-3GEYJ103V"))
    )
    (comp (ref "R35")
      (value "1M0")
      (footprint "rc0603")
      (description "RES 1.00M OHM 1/10W 1% 0603 SMD")
      (fields
        (field (name "MANUFACTURER") "Panasonic Electronic Components")
        (field (name "MANUFACTURER PART NUMBER") "ERJ-3EKF1004V")
      )
      (libsource (lib "Swage") (part "ERJ-3EKF1004V"))
    )
    (comp (ref "R36")
      (value "1M0")
      (footprint "rc0603")
      (description "RES 1.00M OHM 1/10W 1% 0603 SMD")
      (fields
        (field (name "MANUFACTURER") "Panasonic Electronic Components")
        (field (name "MANUFACTURER PART NUMBER") "ERJ-3EKF1004V")
      )
      (libsource (lib "Swage") (part "ERJ-3EKF1004V"))
    )
    (comp (ref "R37")
      (value "715K")
      (footprint "RC0603")
      (description "RES 715K OHM 1/10W 1% 0603 SMD")
      (fields
        (field (name "MANUFACTURER") "Panasonic Electronic Components")
        (field (name "MANUFACTURER PART NUMBER") "ERJ-3EKF7153V")
      )
      (libsource (lib "Swage") (part "ERJ-3EKF7153V"))
    )
    (comp (ref "R38")
      (value "432K")
      (footprint "RC0603")
      (description "RES 432K OHM 1/10W 1% 0603 SMD")
      (fields
        (field (name "MANUFACTURER") "Panasonic Electronic Components")
        (field (name "MANUFACTURER PART NUMBER") "ERJ-3EKF4323V")
      )
      (libsource (lib "Swage") (part "ERJ-3EKF4323V"))
    )
    (comp (ref "R39")
      (value "330R")
      (footprint "RC0805")
      (description "RES 330 OHM 1/8W 5% 0805 SMD")
      (fields
        (field (name "MANUFACTURER") "KOA Speer Electronics")
        (field (name "MANUFACTURER PART NUMBER") "RK73B2ATTD331J")
      )
      (libsource (lib "Swage") (part "ERJ-6GEYJ331V"))
    )
    (comp (ref "R40")
      (value "100R")
      (footprint "RC0603")
      (description "RES 100 OHM 1/10W 5% 0603 SMD")
      (fields
        (field (name "TOLERANCE") "±5%")
        (field (name "MANUFACTURER") "Panasonic Electronic Components")
      )
      (libsource (lib "Swage") (part "ERJ-3GEYJ101V"))
    )
    (comp (ref "R41")
      (value "100R")
      (footprint "RC0603")
      (description "RES 100 OHM 1/10W 5% 0603 SMD")
      (fields
        (field (name "TOLERANCE") "±5%")
        (field (name "MANUFACTURER") "Panasonic Electronic Components")
      )
      (libsource (lib "Swage") (part "ERJ-3GEYJ101V"))
    )
    (comp (ref "R42")
      (value "12R")
      (footprint "RC1206")
      (description "RES 12.0 OHM 1/4W 1% 1206 SMD")
      (fields
        (field (name "MANUFACTURER") "Yageo")
        (field (name "MANUFACTURER PART NUMBER") "RC1206FR-0712RL")
      )
      (libsource (lib "Swage") (part "RC1206FR-0712RL"))
    )
    (comp (ref "R43")
      (value "12R")
      (footprint "RC1206")
      (description "RES 12.0 OHM 1/4W 1% 1206 SMD")
      (fields
        (field (name "MANUFACTURER") "Yageo")
        (field (name "MANUFACTURER PART NUMBER") "RC1206FR-0712RL")
      )
      (libsource (lib "Swage") (part "RC1206FR-0712RL"))
    )
    (comp (ref "R44")
      (value "10K")
      (footprint "RC0603")
      (description "RES 10K OHM 1/10W 5% 0603 SMD")
      (fields
        (field (name "MANUFACTURER") "Panasonic Electronic Components")
        (field (name "MANUFACTURER PART NUMBER") "ERJ-3GEYJ103V")
      )
      (libsource (lib "Swage") (part "ERJ-3GEYJ103V"))
    )
    (comp (ref "R45")
      (value "12R")
      (footprint "RES2512")
      (description "RES 12 OHM 1W 5% 2512")
      (fields
        (field (name "MANUFACTURER") "Stackpole Electronics Inc")
        (field (name "MANUFACTURER PART NUMBER") "RPC2512JT12R0")
        (field (name "POWER (WATTS)") "1W")
      )
      (libsource (lib "Swage") (part "RPC2512JT12R0"))
    )
    (comp (ref "R46")
      (value "0R")
      (footprint "RC0603")
      (description "RES 0.0 OHM 1/10W 0603 SMD")
      (fields (field (name "TOLERANCE") "Jumper") (field (name "MANUFACTURER") "Panasonic - ECG"))
      (libsource (lib "Swage") (part "ERJ-3GEY0R00V"))
    )
    (comp (ref "R47")
      (value "100R")
      (footprint "RC0603")
      (description "RES 100 OHM 1/10W 5% 0603 SMD")
      (fields
        (field (name "TOLERANCE") "±5%")
        (field (name "MANUFACTURER") "Panasonic Electronic Components")
      )
      (libsource (lib "Swage") (part "ERJ-3GEYJ101V"))
    )
    (comp (ref "R50")
      (value "10K (NNP)")
      (footprint "RC0603")
      (description "RES 10K OHM 1/10W 5% 0603 SMD")
      (fields
        (field (name "MANUFACTURER") "Panasonic Electronic Components")
        (field (name "MANUFACTURER PART NUMBER") "ERJ-3GEYJ103V")
      )
      (libsource (lib "Swage") (part "ERJ-3GEYJ103V"))
    )
    (comp (ref "R51")
      (value "10K")
      (footprint "RC0603")
      (description "RES 10K OHM 1/10W 5% 0603 SMD")
      (fields
        (field (name "MANUFACTURER") "Panasonic Electronic Components")
        (field (name "MANUFACTURER PART NUMBER") "ERJ-3GEYJ103V")
      )
      (libsource (lib "Swage") (part "ERJ-3GEYJ103V"))
    )
    (comp (ref "R52")
      (value "10K")
      (footprint "RC0603")
      (description "RES 10K OHM 1/10W 5% 0603 SMD")
      (fields
        (field (name "MANUFACTURER") "Panasonic Electronic Components")
        (field (name "MANUFACTURER PART NUMBER") "ERJ-3GEYJ103V")
      )
      (libsource (lib "Swage") (part "ERJ-3GEYJ103V"))
    )
    (comp (ref "R53")
      (value "10K")
      (footprint "RC0603")
      (description "RES 10K OHM 1/10W 5% 0603 SMD")
      (fields
        (field (name "MANUFACTURER") "Panasonic Electronic Components")
        (field (name "MANUFACTURER PART NUMBER") "ERJ-3GEYJ103V")
      )
      (libsource (lib "Swage") (part "ERJ-3GEYJ103V"))
    )
    (comp (ref "R54")
      (value "2K0")
      (footprint "RC0603")
      (description "RES 2K OHM 1/10W 1% 0603 SMD")
      (fields
        (field (name "MANUFACTURER") "Panasonic Electronic Components")
        (field (name "MANUFACTURER PART NUMBER") "ERJ-3EKF2001V")
      )
      (libsource (lib "Swage") (part "ERJ-3EKF2001V"))
    )
    (comp (ref "R55")
      (value "4k7")
      (footprint "RC0603")
      (description "RES 4.7K OHM 1/10W 5% 0603 SMD")
      (fields
        (field (name "MANUFACTURER") "Panasonic - ECG")
        (field (name "MANUFACTURER PART NUMBER") "ERJ-3GEYJ472V")
      )
      (libsource (lib "Swage") (part "ERJ-3GEYJ472V"))
    )
    (comp (ref "R56")
      (value "4k7")
      (footprint "RC0603")
      (description "RES 4.7K OHM 1/10W 5% 0603 SMD")
      (fields
        (field (name "MANUFACTURER") "Panasonic - ECG")
        (field (name "MANUFACTURER PART NUMBER") "ERJ-3GEYJ472V")
      )
      (libsource (lib "Swage") (part "ERJ-3GEYJ472V"))
    )
    (comp (ref "R57")
      (value "4k7")
      (footprint "RC0603")
      (description "RES 4.7K OHM 1/10W 5% 0603 SMD")
      (fields
        (field (name "MANUFACTURER") "Panasonic - ECG")
        (field (name "MANUFACTURER PART NUMBER") "ERJ-3GEYJ472V")
      )
      (libsource (lib "Swage") (part "ERJ-3GEYJ472V"))
    )
    (comp (ref "R58")
      (value "200K")
      (footprint "RC0603")
      (description "RES 200K OHM 1/10W 5% 0603 SMD")
      (fields
        (field (name "MANUFACTURER") "Panasonic Electronic Components")
        (field (name "MANUFACTURER PART NUMBER") "ERJ-3GEYJ204V")
      )
      (libsource (lib "Swage") (part "ERJ-3GEYJ204V"))
    )
    (comp (ref "R60")
      (value "100R")
      (footprint "RC0603")
      (description "RES 100 OHM 1/10W 5% 0603 SMD")
      (fields
        (field (name "TOLERANCE") "±5%")
        (field (name "MANUFACTURER") "Panasonic Electronic Components")
      )
      (libsource (lib "Swage") (part "ERJ-3GEYJ101V"))
    )
    (comp (ref "R62")
      (value "1K")
      (footprint "rc0603")
      (description "RES 1.0K OHM 1/10W 5% 0603 SMD")
      (fields
        (field (name "MANUFACTURER") "Panasonic Electronic Components")
        (field (name "MANUFACTURER PART NUMBER") "ERJ-3GEYJ102V")
      )
      (libsource (lib "Swage") (part "ERJ-3GEYJ102V"))
    )
    (comp (ref "R63")
      (value "10K")
      (footprint "RC0603")
      (description "RES 10K OHM 1/10W 5% 0603 SMD")
      (fields
        (field (name "MANUFACTURER") "Panasonic Electronic Components")
        (field (name "MANUFACTURER PART NUMBER") "ERJ-3GEYJ103V")
      )
      (libsource (lib "Swage") (part "ERJ-3GEYJ103V"))
    )
    (comp (ref "R64")
      (value "3M65")
      (footprint "RC0603")
      (description "RES 3M65 OHM 1/10W 1% 0603 SMD")
      (fields
        (field (name "MANUFACTURER") "Samsung")
        (field (name "MANUFACTURER PART NUMBER") "RC1608F3654CS")
      )
      (libsource (lib "Swage") (part "RC1608F3654CS"))
    )
    (comp (ref "R65")
      (value "715K")
      (footprint "RC0603")
      (description "RES 715K OHM 1/10W 1% 0603 SMD")
      (fields
        (field (name "MANUFACTURER") "Panasonic Electronic Components")
        (field (name "MANUFACTURER PART NUMBER") "ERJ-3EKF7153V")
      )
      (libsource (lib "Swage") (part "ERJ-3EKF7153V"))
    )
    (comp (ref "R66")
      (value "100R")
      (footprint "RC0603")
      (description "RES 100 OHM 1/10W 5% 0603 SMD")
      (fields
        (field (name "TOLERANCE") "±5%")
        (field (name "MANUFACTURER") "Panasonic Electronic Components")
      )
      (libsource (lib "Swage") (part "ERJ-3GEYJ101V"))
    )
    (comp (ref "R67")
      (value "100K")
      (footprint "RC0603")
      (description "RES 100K OHM 1/10W 5% 0603 SMD")
      (fields
        (field (name "MANUFACTURER") "Panasonic Electronic Components")
        (field (name "MANUFACTURER PART NUMBER") "ERJ-3GEYJ104V")
      )
      (libsource (lib "Swage") (part "ERJ-3GEYJ104V"))
    )
    (comp (ref "R68")
      (value "4k7")
      (footprint "RC0603")
      (description "RES 4.7K OHM 1/10W 5% 0603 SMD")
      (fields
        (field (name "MANUFACTURER") "Panasonic - ECG")
        (field (name "MANUFACTURER PART NUMBER") "ERJ-3GEYJ472V")
      )
      (libsource (lib "Swage") (part "ERJ-3GEYJ472V"))
    )
    (comp (ref "R69")
      (value "10K")
      (footprint "RC0603")
      (description "RES 10K OHM 1/10W 5% 0603 SMD")
      (fields
        (field (name "MANUFACTURER") "Panasonic Electronic Components")
        (field (name "MANUFACTURER PART NUMBER") "ERJ-3GEYJ103V")
      )
      (libsource (lib "Swage") (part "ERJ-3GEYJ103V"))
    )
    (comp (ref "RAD1")
      (value "RF 200 Snappy Transceiver")
      (footprint "RF200")
      (description "Synapse RF200PF1 Snappy Transceiver")
      (fields
        (field (name "MANUFACTURER") "Synapse Wireless")
        (field (name "MANUFACTURER PART NUMBER") "RF200PF1")
      )
      (libsource (lib "Swage") (part "RF 200 Snappy Transceiver"))
    )
    (comp (ref "SP1")
      (value "MPT3.6-300")
      (footprint "SOLAR_PANEL_FLEX")
      (description "Solar Panel, Flexible, 3.6V and 4.8V footprints")
      (fields (field (name "MANUFACTURER") "PowerFilm Solar"))
      (libsource (lib "Swage") (part "SOLAR_PANEL"))
    )
    (comp (ref "SW1")
      (value "MK15-E-2")
      (footprint "MK15-E-2")
      (description "SWITCH REED MAG SMT 25-30 AT")
      (fields (field (name "MANUFACTURER") "Standex-Meder Electronics"))
      (libsource (lib "Swage") (part "MK15-E-2"))
    )
    (comp (ref "TP1")
      (value "Testpoint")
      (footprint "TestPoint")
      (libsource (lib "Swage") (part "Testpoint"))
    )
    (comp (ref "TP2")
      (value "Testpoint")
      (footprint "TestPoint")
      (libsource (lib "Swage") (part "Testpoint"))
    )
    (comp (ref "TP3")
      (value "Testpoint")
      (footprint "TestPoint")
      (libsource (lib "Swage") (part "Testpoint"))
    )
    (comp (ref "TP4")
      (value "Testpoint")
      (footprint "TestPoint")
      (libsource (lib "Swage") (part "Testpoint"))
    )
    (comp (ref "TP5")
      (value "Testpoint")
      (footprint "TestPoint")
      (libsource (lib "Swage") (part "Testpoint"))
    )
    (comp (ref "TP6")
      (value "Testpoint")
      (footprint "TestPoint")
      (libsource (lib "Swage") (part "Testpoint"))
    )
    (comp (ref "TP7")
      (value "Testpoint")
      (footprint "TestPoint")
      (libsource (lib "Swage") (part "Testpoint"))
    )
    (comp (ref "TP8")
      (value "Testpoint")
      (footprint "TestPoint")
      (libsource (lib "Swage") (part "Testpoint"))
    )
    (comp (ref "TP9")
      (value "Testpoint")
      (footprint "TestPoint")
      (libsource (lib "Swage") (part "Testpoint"))
    )
    (comp (ref "TP10")
      (value "Testpoint")
      (footprint "TestPoint")
      (libsource (lib "Swage") (part "Testpoint"))
    )
    (comp (ref "TP11")
      (value "Testpoint")
      (footprint "TestPoint")
      (libsource (lib "Swage") (part "Testpoint"))
    )
    (comp (ref "TP12")
      (value "Testpoint")
      (footprint "TestPoint")
      (libsource (lib "Swage") (part "Testpoint"))
    )
    (comp (ref "TP13")
      (value "Testpoint")
      (footprint "TestPoint")
      (libsource (lib "Swage") (part "Testpoint"))
    )
    (comp (ref "TP14")
      (value "Testpoint")
      (footprint "TestPoint")
      (libsource (lib "Swage") (part "Testpoint"))
    )
    (comp (ref "TP15")
      (value "Testpoint")
      (footprint "TestPoint")
      (libsource (lib "Swage") (part "Testpoint"))
    )
    (comp (ref "TP16")
      (value "Testpoint")
      (footprint "TestPoint")
      (libsource (lib "Swage") (part "Testpoint"))
    )
    (comp (ref "TP17")
      (value "Testpoint")
      (footprint "TestPoint")
      (libsource (lib "Swage") (part "Testpoint"))
    )
    (comp (ref "TP18")
      (value "Testpoint")
      (footprint "TestPoint")
      (libsource (lib "Swage") (part "Testpoint"))
    )
    (comp (ref "TP19")
      (value "Testpoint")
      (footprint "TestPoint")
      (libsource (lib "Swage") (part "Testpoint"))
    )
    (comp (ref "TP20")
      (value "Testpoint")
      (footprint "TestPoint")
      (libsource (lib "Swage") (part "Testpoint"))
    )
    (comp (ref "TP21")
      (value "Testpoint")
      (footprint "TestPoint")
      (libsource (lib "Swage") (part "Testpoint"))
    )
    (comp (ref "TP22")
      (value "Testpoint")
      (footprint "TestPoint")
      (libsource (lib "Swage") (part "Testpoint"))
    )
    (comp (ref "TP23")
      (value "Testpoint")
      (footprint "TestPoint")
      (libsource (lib "Swage") (part "Testpoint"))
    )
    (comp (ref "TP24")
      (value "Testpoint")
      (footprint "TestPoint")
      (libsource (lib "Swage") (part "Testpoint"))
    )
    (comp (ref "U1")
      (value "LTC3526LBEDC-2")
      (footprint "LTC3526")
      (description "IC REG BOOST SYNC ADJ 0.55A 6DFN")
      (fields
        (field (name "MANUFACTURER") "Linear Technology")
        (field (name "MANUFACTURER PART NUMBER") "LTC3526LBEDC-2#TRMPBF")
      )
      (libsource (lib "Swage") (part "LTC3526LBEDC-2"))
    )
    (comp (ref "U2")
      (value "BQ25504RGT")
      (footprint "BQ25504")
      (description "IC ENERGY HARV CTRLR BATT 16QFN")
      (fields
        (field (name "MANUFACTURER") "Texas Instruments")
        (field (name "MANUFACTURER PART NUMBER") "BQ25504RGTT")
      )
      (libsource (lib "Swage") (part "BQ25504RGTT"))
    )
    (comp (ref "U3")
      (value "FDG6342L")
      (footprint "TS5A3160")
      (description "IC LOAD SWITCH INTEGRATED SC70-6")
      (fields (field (name "MANUFACTURER") "Fairchild Semiconductor"))
      (libsource (lib "Swage") (part "FDG6342L"))
    )
    (comp (ref "U5")
      (value "FDG6342L")
      (footprint "TS5A3160")
      (description "IC LOAD SWITCH INTEGRATED SC70-6")
      (fields (field (name "MANUFACTURER") "Fairchild Semiconductor"))
      (libsource (lib "Swage") (part "FDG6342L"))
    )
    (comp (ref "U6")
      (value "DS2482S-100+")
      (footprint "SOIC127P580X153-8N")
      (description "IC BRIDGE I2C TO 1-WIRE 8-SOIC")
      (fields (field (name "MANUFACTURER") "Maxim Integrated"))
      (libsource (lib "Swage") (part "DS2482S-100+"))
    )
    (comp (ref "U8")
      (value "NLAS4157D")
      (footprint "TS5A3160")
      (description "IC SWITCH SPDT SC88")
      (fields
        (field (name "MANUFACTURER") "ON Semiconductor")
        (field (name "MANUFACTURER PART NUMBER") "NLAS4157DFT2G")
      )
      (libsource (lib "Swage") (part "NLAS4157DFT2G"))
    )
    (comp (ref "U9")
      (value "NLAS4157D")
      (footprint "TS5A3160")
      (description "IC SWITCH SPDT SC88")
      (fields
        (field (name "MANUFACTURER") "ON Semiconductor")
        (field (name "MANUFACTURER PART NUMBER") "NLAS4157DFT2G")
      )
      (libsource (lib "") (part "NLAS4157DFT2G_1"))
    )
    (comp (ref "U10")
      (value "PCA9306DP")
      (footprint "TSOP65P640X120-8N")
      (description "IC LEVEL TRANSLATOR - TSSOP8")
      (fields
        (field (name "MANUFACTURER") "ON Semiconductor")
        (field (name "MANUFACTURER PART NUMBER") "PCA9306DTR2G")
      )
      (libsource (lib "Swage") (part "PCA9306DP"))
    )
    (comp (ref "U11")
      (value "TPS3808G01DBV")
      (footprint "SOT95P270X145-6N")
      (description "Low Quiescent Current, Programmable-Delay  Supervisory Circuit")
      (fields
        (field (name "MANUFACTURER") "Texas Instruments")
        (field (name "MANUFACTURER PART NUMBER") "TPS3808G01DBVR")
      )
      (libsource (lib "Swage") (part "TPS3808G01DBV"))
    )
  )
  (nets
    (net (code "1") (name "/A2D_VBAT") (class "Default")
      (node (ref "P6") (pin "12") (pintype "passive"))
      (node (ref "R35") (pin "2") (pinfunction "2_2") (pintype "passive"))
      (node (ref "R37") (pin "2") (pinfunction "2_2") (pintype "passive"))
      (node (ref "RAD1") (pin "13") (pinfunction "GPIO11/ADC0/PF0_13") (pintype "passive"))
      (node (ref "TP11") (pin "1") (pinfunction "1_1") (pintype "passive"))
    )
    (net (code "2") (name "/A2D_VSOLAR") (class "Default")
      (node (ref "P6") (pin "7") (pintype "passive"))
      (node (ref "Q6") (pin "1") (pinfunction "D_1") (pintype "passive"))
      (node (ref "R36") (pin "2") (pinfunction "2_2") (pintype "passive"))
      (node (ref "R38") (pin "2") (pinfunction "2_2") (pintype "passive"))
      (node (ref "RAD1") (pin "18") (pinfunction "GPIO16/ADC5/TMS_18") (pintype "passive"))
      (node (ref "TP12") (pin "1") (pinfunction "1_1") (pintype "passive"))
    )
    (net (code "3") (name "/DQ_CHANNEL_0") (class "Default")
      (node (ref "D2") (pin "2") (pinfunction "2_2") (pintype "passive"))
      (node (ref "D8") (pin "2") (pinfunction "2_2") (pintype "passive"))
      (node (ref "P4") (pin "3") (pinfunction "DESIGNATOR=3_3") (pintype "passive"))
      (node (ref "P5") (pin "2") (pinfunction "2_2") (pintype "passive"))
      (node (ref "U8") (pin "4") (pinfunction "4_4") (pintype "passive"))
    )
    (net (code "4") (name "/DQ_CONNECT") (class "Default")
      (node (ref "P6") (pin "9") (pintype "passive"))
      (node (ref "R66") (pin "1") (pinfunction "1_1") (pintype "passive"))
      (node (ref "RAD1") (pin "16") (pinfunction "GPIO14/XCK0/AIN0_16") (pintype "passive"))
      (node (ref "TP17") (pin "1") (pinfunction "1_1") (pintype "passive"))
    )
    (net (code "5") (name "/DQ_DEFIB") (class "Default")
      (node (ref "P7") (pin "11") (pintype "passive"))
      (node (ref "R15") (pin "1") (pinfunction "1_1") (pintype "passive"))
      (node (ref "RAD1") (pin "11") (pinfunction "GPIO9/ICP1/PD4_11") (pintype "passive"))
      (node (ref "TP16") (pin "1") (pinfunction "1_1") (pintype "passive"))
    )
    (net (code "6") (name "/DQ_MASTER") (class "Default")
      (node (ref "Q1") (pin "D") (pinfunction "D_D") (pintype "passive"))
      (node (ref "R18") (pin "2") (pinfunction "2_2") (pintype "passive"))
      (node (ref "R54") (pin "2") (pinfunction "2_2") (pintype "passive"))
      (node (ref "U6") (pin "2") (pinfunction "IO_2") (pintype "passive"))
      (node (ref "U8") (pin "1") (pinfunction "NO_1") (pintype "passive"))
    )
    (net (code "7") (name "/GPIO7") (class "Default")
      (node (ref "P7") (pin "9") (pintype "passive"))
      (node (ref "R27") (pin "1") (pinfunction "1_1") (pintype "passive"))
      (node (ref "RAD1") (pin "9") (pinfunction "GPIO7/RXD1/PD2_9") (pintype "passive"))
    )
    (net (code "8") (name "/GPIO8") (class "Default")
      (node (ref "P7") (pin "10") (pintype "passive"))
      (node (ref "R28") (pin "1") (pinfunction "1_1") (pintype "passive"))
      (node (ref "RAD1") (pin "10") (pinfunction "GPIO8/TXD1/PD3_10") (pintype "passive"))
    )
    (net (code "9") (name "/GPIO15") (class "Default")
      (node (ref "P6") (pin "8") (pintype "passive"))
      (node (ref "R41") (pin "2") (pinfunction "2_2") (pintype "passive"))
      (node (ref "RAD1") (pin "17") (pinfunction "GPIO15/ADC4/TCK_17") (pintype "passive"))
    )
    (net (code "10") (name "/GPIO19") (class "Default")
      (node (ref "P6") (pin "3") (pintype "passive"))
      (node (ref "R40") (pin "2") (pinfunction "2_2") (pintype "passive"))
      (node (ref "RAD1") (pin "22") (pinfunction "GPIO19/OC3A/AIN1_22") (pintype "passive"))
    )
    (net (code "11") (name "/HW_VER1") (class "Default")
      (node (ref "P7") (pin "3") (pintype "passive"))
      (node (ref "R50") (pin "1") (pinfunction "1_1") (pintype "passive"))
      (node (ref "RAD1") (pin "3") (pinfunction "GPIO1/PCINT6/PB6_3") (pintype "passive"))
      (node (ref "TP21") (pin "1") (pinfunction "1_1") (pintype "passive"))
    )
    (net (code "12") (name "/HW_VER2") (class "Default")
      (node (ref "P7") (pin "5") (pintype "passive"))
      (node (ref "R51") (pin "1") (pinfunction "1_1") (pintype "passive"))
      (node (ref "RAD1") (pin "5") (pinfunction "GPIO3/RXD0/PE0_5") (pintype "passive"))
      (node (ref "TP22") (pin "1") (pinfunction "1_1") (pintype "passive"))
    )
    (net (code "13") (name "/HW_VER3") (class "Default")
      (node (ref "P7") (pin "6") (pintype "passive"))
      (node (ref "R52") (pin "1") (pinfunction "1_1") (pintype "passive"))
      (node (ref "RAD1") (pin "6") (pinfunction "GPIO4/TXD0/PE1_6") (pintype "passive"))
      (node (ref "TP23") (pin "1") (pinfunction "1_1") (pintype "passive"))
    )
    (net (code "14") (name "/HW_VER4") (class "Default")
      (node (ref "P7") (pin "8") (pintype "passive"))
      (node (ref "R53") (pin "1") (pinfunction "1_1") (pintype "passive"))
      (node (ref "RAD1") (pin "8") (pinfunction "GPIO6/INT5/PE5_8") (pintype "passive"))
      (node (ref "TP24") (pin "1") (pinfunction "1_1") (pintype "passive"))
    )
    (net (code "15") (name "/I2C_SCL") (class "Default")
      (node (ref "P6") (pin "5") (pintype "passive"))
      (node (ref "R68") (pin "1") (pinfunction "1_1") (pintype "passive"))
      (node (ref "RAD1") (pin "20") (pinfunction "GPIO18/ADC7/TDI_20") (pintype "passive"))
      (node (ref "TP15") (pin "1") (pinfunction "1_1") (pintype "passive"))
      (node (ref "U10") (pin "3") (pinfunction "SCL1_3") (pintype "passive"))
    )
    (net (code "16") (name "/I2C_SDA") (class "Default")
      (node (ref "P6") (pin "6") (pintype "passive"))
      (node (ref "R55") (pin "1") (pinfunction "1_1") (pintype "passive"))
      (node (ref "RAD1") (pin "19") (pinfunction "GPIO17/ADC6/TDO_19") (pintype "passive"))
      (node (ref "TP14") (pin "1") (pinfunction "1_1") (pintype "passive"))
      (node (ref "U10") (pin "4") (pinfunction "SDA1_4") (pintype "passive"))
    )
    (net (code "17") (name "/LED1") (class "Default")
      (node (ref "P7") (pin "7") (pintype "passive"))
      (node (ref "R25") (pin "1") (pinfunction "1_1") (pintype "passive"))
      (node (ref "RAD1") (pin "7") (pinfunction "GPIO5/INT4/PE4_7") (pintype "passive"))
      (node (ref "TP7") (pin "1") (pinfunction "1_1") (pintype "passive"))
    )
    (net (code "18") (name "/LED2") (class "Default")
      (node (ref "P7") (pin "2") (pintype "passive"))
      (node (ref "R26") (pin "1") (pinfunction "1_1") (pintype "passive"))
      (node (ref "RAD1") (pin "2") (pinfunction "GPIO0/PCINT7/PB7_2") (pintype "passive"))
      (node (ref "TP8") (pin "1") (pinfunction "1_1") (pintype "passive"))
    )
    (net (code "19") (name "/LED3") (class "Default")
      (node (ref "P7") (pin "4") (pintype "passive"))
      (node (ref "R30") (pin "1") (pinfunction "1_1") (pintype "passive"))
      (node (ref "RAD1") (pin "4") (pinfunction "GPIO2/PCINT5/PB5_4") (pintype "passive"))
      (node (ref "TP9") (pin "1") (pinfunction "1_1") (pintype "passive"))
    )
    (net (code "20") (name "/LED4") (class "Default")
      (node (ref "P6") (pin "10") (pintype "passive"))
      (node (ref "R33") (pin "1") (pinfunction "1_1") (pintype "passive"))
      (node (ref "RAD1") (pin "15") (pinfunction "GPIO13/ADC2/PF2_15") (pintype "passive"))
      (node (ref "TP10") (pin "1") (pinfunction "1_1") (pintype "passive"))
    )
    (net (code "21") (name "/N_5V_OFF") (class "Default")
      (node (ref "P7") (pin "12") (pintype "passive"))
      (node (ref "RAD1") (pin "12") (pinfunction "GPIO10/INT7/CLK0_12") (pintype "passive"))
      (node (ref "TP13") (pin "1") (pinfunction "1_1") (pintype "passive"))
      (node (ref "U1") (pin "4") (pinfunction "~{SHDN}_4") (pintype "passive"))
    )
    (net (code "22") (name "/POWER_IN") (class "Default")
      (node (ref "P4") (pin "7") (pinfunction "DESIGNATOR=7_7") (pintype "passive"))
      (node (ref "P5") (pin "1") (pinfunction "1_1") (pintype "passive"))
      (node (ref "R45") (pin "1") (pinfunction "1_1") (pintype "passive"))
    )
    (net (code "23") (name "/RXD_RF200") (class "Default")
      (node (ref "D13") (pin "3") (pinfunction "3_3") (pintype "passive"))
      (node (ref "P2") (pin "2") (pinfunction "2_2") (pintype "passive"))
      (node (ref "P4") (pin "11") (pinfunction "DESIGNATOR=11_11") (pintype "passive"))
      (node (ref "R27") (pin "2") (pinfunction "2_2") (pintype "passive"))
    )
    (net (code "24") (name "/SPARE1") (class "Default")
      (node (ref "P4") (pin "4") (pinfunction "DESIGNATOR=4_4") (pintype "passive"))
      (node (ref "R44") (pin "2") (pinfunction "2_2") (pintype "passive"))
    )
    (net (code "25") (name "/TXD_RF200") (class "Default")
      (node (ref "D11") (pin "3") (pinfunction "3_3") (pintype "passive"))
      (node (ref "P2") (pin "3") (pinfunction "3_3") (pintype "passive"))
      (node (ref "P4") (pin "9") (pinfunction "DESIGNATOR=9_9") (pintype "passive"))
      (node (ref "R28") (pin "2") (pinfunction "2_2") (pintype "passive"))
    )
    (net (code "26") (name "/VBAT_FUSED") (class "Default")
      (node (ref "F1") (pin "1") (pinfunction "1_1") (pintype "passive"))
      (node (ref "R13") (pin "2") (pinfunction "2_2") (pintype "passive"))
      (node (ref "R42") (pin "1") (pinfunction "1_1") (pintype "passive"))
      (node (ref "TP3") (pin "1") (pinfunction "1_1") (pintype "passive"))
      (node (ref "U3") (pin "4") (pinfunction "VIN_4") (pintype "passive"))
    )
    (net (code "27") (name "/VBAT_OK") (class "Default")
      (node (ref "D10") (pin "2") (pinfunction "2_2") (pintype "passive"))
      (node (ref "D9") (pin "1") (pintype "passive"))
      (node (ref "P1") (pin "1") (pinfunction "1_1") (pintype "passive"))
      (node (ref "R20") (pin "1") (pinfunction "1_1") (pintype "passive"))
      (node (ref "R47") (pin "2") (pinfunction "2_2") (pintype "passive"))
      (node (ref "R62") (pin "2") (pinfunction "2_2") (pintype "passive"))
      (node (ref "U3") (pin "5") (pinfunction "ON/~{OFF}_5") (pintype "passive"))
    )
    (net (code "28") (name "/VBAT_POS") (class "Default")
      (node (ref "BATT1") (pin "1") (pinfunction "1_1") (pintype "passive"))
      (node (ref "BATT1") (pin "2") (pinfunction "2_2") (pintype "passive"))
      (node (ref "BATT1") (pin "3") (pinfunction "3_3") (pintype "passive"))
      (node (ref "BATT1") (pin "4") (pinfunction "4_4") (pintype "passive"))
      (node (ref "F1") (pin "2") (pinfunction "2_2") (pintype "passive"))
      (node (ref "F3") (pin "1") (pinfunction "1_1") (pintype "passive"))
      (node (ref "J1") (pin "1") (pinfunction "1_1") (pintype "passive"))
    )
    (net (code "29") (name "/VBAT_SW_SENSE") (class "Default")
      (node (ref "P4") (pin "5") (pinfunction "DESIGNATOR=5_5") (pintype "passive"))
      (node (ref "R43") (pin "2") (pinfunction "2_2") (pintype "passive"))
    )
    (net (code "30") (name "/VIN_SOLAR") (class "Default")
      (node (ref "C2") (pin "2") (pinfunction "2_2") (pintype "passive"))
      (node (ref "D15") (pin "1") (pintype "passive"))
      (node (ref "D3") (pin "2") (pinfunction "K_2") (pintype "passive"))
      (node (ref "D4") (pin "2") (pinfunction "K_2") (pintype "passive"))
      (node (ref "D5") (pin "2") (pinfunction "2_2") (pintype "passive"))
      (node (ref "D6") (pin "1") (pintype "passive"))
      (node (ref "F2") (pin "1") (pinfunction "1_1") (pintype "passive"))
      (node (ref "L2") (pin "A") (pinfunction "A_A") (pintype "passive"))
      (node (ref "R2") (pin "2") (pinfunction "2_2") (pintype "passive"))
      (node (ref "R36") (pin "1") (pinfunction "1_1") (pintype "passive"))
      (node (ref "TP1") (pin "1") (pinfunction "1_1") (pintype "passive"))
      (node (ref "U2") (pin "2") (pinfunction "VIN_DC_2") (pintype "passive"))
    )
    (net (code "31") (name "/VSTOR") (class "Default")
      (node (ref "C3") (pin "2") (pinfunction "2_2") (pintype "passive"))
      (node (ref "TP2") (pin "1") (pinfunction "1_1") (pintype "passive"))
      (node (ref "U2") (pin "15") (pinfunction "VSTOR_15") (pintype "passive"))
    )
    (net (code "32") (name "/nBOOT_CNE") (class "Default")
      (node (ref "D14") (pin "3") (pinfunction "3_3") (pintype "passive"))
      (node (ref "P4") (pin "10") (pinfunction "DESIGNATOR=10_10") (pintype "passive"))
      (node (ref "R41") (pin "1") (pinfunction "1_1") (pintype "passive"))
    )
    (net (code "33") (name "/nRESET") (class "Default")
      (node (ref "P6") (pin "2") (pintype "passive"))
      (node (ref "R69") (pin "2") (pinfunction "2_2") (pintype "passive"))
      (node (ref "RAD1") (pin "23") (pinfunction "nRESET_23") (pintype "passive"))
      (node (ref "TP20") (pin "1") (pinfunction "1_1") (pintype "passive"))
      (node (ref "U11") (pin "1") (pinfunction "/RESET_1") (pintype "passive"))
      (node (ref "U9") (pin "4") (pinfunction "4_4") (pintype "passive"))
    )
    (net (code "34") (name "/nRESET_CNE") (class "Default")
      (node (ref "D12") (pin "3") (pinfunction "3_3") (pintype "passive"))
      (node (ref "P4") (pin "1") (pinfunction "DESIGNATOR=1_1") (pintype "passive"))
      (node (ref "R40") (pin "1") (pinfunction "1_1") (pintype "passive"))
    )
    (net (code "35") (name "5V") (class "Default")
      (node (ref "C1") (pin "2") (pinfunction "2_2") (pintype "passive"))
      (node (ref "C10") (pin "2") (pinfunction "2_2") (pintype "passive"))
      (node (ref "C5") (pin "2") (pinfunction "2_2") (pintype "passive"))
      (node (ref "D16") (pin "1") (pinfunction "A_1") (pintype "passive"))
      (node (ref "P4") (pin "8") (pinfunction "DESIGNATOR=8_8") (pintype "passive"))
      (node (ref "R1") (pin "2") (pinfunction "2_2") (pintype "passive"))
      (node (ref "R16") (pin "2") (pinfunction "2_2") (pintype "passive"))
      (node (ref "R17") (pin "1") (pinfunction "1_1") (pintype "passive"))
      (node (ref "R21") (pin "1") (pinfunction "1_1") (pintype "passive"))
      (node (ref "R22") (pin "1") (pinfunction "1_1") (pintype "passive"))
      (node (ref "R29") (pin "1") (pinfunction "1_1") (pintype "passive"))
      (node (ref "R32") (pin "1") (pinfunction "1_1") (pintype "passive"))
      (node (ref "R46") (pin "1") (pinfunction "1_1") (pintype "passive"))
      (node (ref "R54") (pin "1") (pinfunction "1_1") (pintype "passive"))
      (node (ref "R56") (pin "2") (pinfunction "2_2") (pintype "passive"))
      (node (ref "R57") (pin "2") (pinfunction "2_2") (pintype "passive"))
      (node (ref "R58") (pin "1") (pinfunction "1_1") (pintype "passive"))
      (node (ref "TP4") (pin "1") (pinfunction "1_1") (pintype "passive"))
      (node (ref "U1") (pin "6") (pinfunction "VOUT_6") (pintype "passive"))
      (node (ref "U5") (pin "4") (pinfunction "VIN_4") (pintype "passive"))
      (node (ref "U6") (pin "1") (pinfunction "VCC_1") (pintype "passive"))
    )
    (net (code "36") (name "CONSTANT_POWER") (class "Default")
      (node (ref "C11") (pin "1") (pinfunction "1_1") (pintype "passive"))
      (node (ref "D16") (pin "3") (pinfunction "K_3") (pintype "passive"))
      (node (ref "R46") (pin "2") (pinfunction "2_2") (pintype "passive"))
      (node (ref "TP5") (pin "1") (pinfunction "1_1") (pintype "passive"))
      (node (ref "U8") (pin "5") (pinfunction "5_5") (pintype "passive"))
    )
    (net (code "37") (name "GND") (class "Default")
      (node (ref "BATT1") (pin "5") (pinfunction "5_5") (pintype "passive"))
      (node (ref "BATT1") (pin "6") (pinfunction "6_6") (pintype "passive"))
      (node (ref "BATT1") (pin "7") (pinfunction "7_7") (pintype "passive"))
      (node (ref "BATT1") (pin "8") (pinfunction "8_8") (pintype "passive"))
      (node (ref "C10") (pin "1") (pinfunction "1_1") (pintype "passive"))
      (node (ref "C11") (pin "2") (pinfunction "2_2") (pintype "passive"))
      (node (ref "C2") (pin "1") (pinfunction "1_1") (pintype "passive"))
      (node (ref "C20") (pin "1") (pinfunction "1_1") (pintype "passive"))
      (node (ref "C3") (pin "1") (pinfunction "1_1") (pintype "passive"))
      (node (ref "C4") (pin "1") (pinfunction "1_1") (pintype "passive"))
      (node (ref "C5") (pin "1") (pinfunction "1_1") (pintype "passive"))
      (node (ref "C50") (pin "1") (pinfunction "1_1") (pintype "passive"))
      (node (ref "C51") (pin "1") (pinfunction "1_1") (pintype "passive"))
      (node (ref "C53") (pin "1") (pinfunction "1_1") (pintype "passive"))
      (node (ref "C54") (pin "1") (pinfunction "1_1") (pintype "passive"))
      (node (ref "C6") (pin "1") (pinfunction "1_1") (pintype "passive"))
      (node (ref "C8") (pin "1") (pinfunction "1_1") (pintype "passive"))
      (node (ref "C9") (pin "1") (pinfunction "1_1") (pintype "passive"))
      (node (ref "D10") (pin "1") (pintype "passive"))
      (node (ref "D11") (pin "1") (pinfunction "A_1") (pintype "passive"))
      (node (ref "D12") (pin "1") (pinfunction "A_1") (pintype "passive"))
      (node (ref "D13") (pin "1") (pinfunction "A_1") (pintype "passive"))
      (node (ref "D14") (pin "1") (pinfunction "A_1") (pintype "passive"))
      (node (ref "D15") (pin "2") (pintype "passive"))
      (node (ref "D2") (pin "1") (pintype "passive"))
      (node (ref "D5") (pin "1") (pintype "passive"))
      (node (ref "D6") (pin "2") (pinfunction "2_2") (pintype "passive"))
      (node (ref "D8") (pin "1") (pintype "passive"))
      (node (ref "D9") (pin "2") (pinfunction "2_2") (pintype "passive"))
      (node (ref "J1") (pin "2") (pinfunction "2_2") (pintype "passive"))
      (node (ref "MH3") (pin "1") (pinfunction "1_1") (pintype "passive"))
      (node (ref "P1") (pin "2") (pinfunction "2_2") (pintype "passive"))
      (node (ref "P2") (pin "4") (pinfunction "4_4") (pintype "passive"))
      (node (ref "P3") (pin "1") (pinfunction "1_1") (pintype "passive"))
      (node (ref "P4") (pin "12") (pinfunction "DESIGNATOR=12_12") (pintype "passive"))
      (node (ref "P4") (pin "2") (pinfunction "DESIGNATOR=2_2") (pintype "passive"))
      (node (ref "P5") (pin "3") (pinfunction "3_3") (pintype "passive"))
      (node (ref "P6") (pin "1") (pintype "passive"))
      (node (ref "P7") (pin "1") (pintype "passive"))
      (node (ref "Q2") (pin "2") (pinfunction "S_2") (pintype "passive"))
      (node (ref "Q3") (pin "2") (pinfunction "S_2") (pintype "passive"))
      (node (ref "Q4") (pin "2") (pinfunction "S_2") (pintype "passive"))
      (node (ref "Q5") (pin "2") (pinfunction "S_2") (pintype "passive"))
      (node (ref "Q6") (pin "2") (pinfunction "S_2") (pintype "passive"))
      (node (ref "R10") (pin "2") (pinfunction "2_2") (pintype "passive"))
      (node (ref "R11") (pin "2") (pinfunction "2_2") (pintype "passive"))
      (node (ref "R12") (pin "2") (pinfunction "2_2") (pintype "passive"))
      (node (ref "R19") (pin "2") (pinfunction "2_2") (pintype "passive"))
      (node (ref "R23") (pin "2") (pinfunction "2_2") (pintype "passive"))
      (node (ref "R24") (pin "2") (pinfunction "2_2") (pintype "passive"))
      (node (ref "R3") (pin "2") (pinfunction "2_2") (pintype "passive"))
      (node (ref "R31") (pin "2") (pinfunction "2_2") (pintype "passive"))
      (node (ref "R34") (pin "2") (pinfunction "2_2") (pintype "passive"))
      (node (ref "R37") (pin "1") (pinfunction "1_1") (pintype "passive"))
      (node (ref "R38") (pin "1") (pinfunction "1_1") (pintype "passive"))
      (node (ref "R39") (pin "2") (pinfunction "2_2") (pintype "passive"))
      (node (ref "R44") (pin "1") (pinfunction "1_1") (pintype "passive"))
      (node (ref "R50") (pin "2") (pinfunction "2_2") (pintype "passive"))
      (node (ref "R51") (pin "2") (pinfunction "2_2") (pintype "passive"))
      (node (ref "R52") (pin "2") (pinfunction "2_2") (pintype "passive"))
      (node (ref "R53") (pin "2") (pinfunction "2_2") (pintype "passive"))
      (node (ref "R60") (pin "2") (pinfunction "2_2") (pintype "passive"))
      (node (ref "R65") (pin "1") (pinfunction "1_1") (pintype "passive"))
      (node (ref "R67") (pin "2") (pinfunction "2_2") (pintype "passive"))
      (node (ref "R7") (pin "2") (pinfunction "2_2") (pintype "passive"))
      (node (ref "RAD1") (pin "1") (pinfunction "GND_1") (pintype "passive"))
      (node (ref "RAD1") (pin "24") (pinfunction "GND_24") (pintype "passive"))
      (node (ref "SP1") (pin "1") (pinfunction "GND_1") (pintype "passive"))
      (node (ref "SW1") (pin "1") (pinfunction "1_1") (pintype "passive"))
      (node (ref "TP18") (pin "1") (pinfunction "1_1") (pintype "passive"))
      (node (ref "U1") (pin "2") (pinfunction "GND_2") (pintype "passive"))
      (node (ref "U1") (pin "7") (pinfunction "DIE_7") (pintype "passive"))
      (node (ref "U10") (pin "1") (pinfunction "GND_1") (pintype "passive"))
      (node (ref "U11") (pin "2") (pinfunction "GND_2") (pintype "passive"))
      (node (ref "U2") (pin "1") (pinfunction "GND_1") (pintype "passive"))
      (node (ref "U2") (pin "12") (pinfunction "AGND_12") (pintype "passive"))
      (node (ref "U2") (pin "13") (pinfunction "GND_13") (pintype "passive"))
      (node (ref "U2") (pin "17") (pinfunction "DIE_17") (pintype "passive"))
      (node (ref "U2") (pin "5") (pinfunction "OT_PROG_5") (pintype "passive"))
      (node (ref "U5") (pin "1") (pinfunction "R2_1") (pintype "passive"))
      (node (ref "U6") (pin "3") (pinfunction "GND_3") (pintype "passive"))
      (node (ref "U6") (pin "7") (pinfunction "AD1_7") (pintype "passive"))
      (node (ref "U6") (pin "8") (pinfunction "AD0_8") (pintype "passive"))
      (node (ref "U8") (pin "2") (pinfunction "GND_2") (pintype "passive"))
      (node (ref "U9") (pin "2") (pinfunction "GND_2") (pintype "passive"))
    )
    (net (code "38") (name "Net-(D1-A)") (class "Default")
      (node (ref "D1") (pin "1") (pinfunction "A_1") (pintype "passive"))
      (node (ref "P2") (pin "1") (pinfunction "1_1") (pintype "passive"))
      (node (ref "R45") (pin "2") (pinfunction "2_2") (pintype "passive"))
    )
    (net (code "39") (name "Net-(D1-K)") (class "Default")
      (node (ref "D1") (pin "2") (pinfunction "K_2") (pintype "passive"))
      (node (ref "F2") (pin "2") (pinfunction "2_2") (pintype "passive"))
    )
    (net (code "40") (name "Net-(D3-A)") (class "Default")
      (node (ref "D3") (pin "1") (pinfunction "A_1") (pintype "passive"))
      (node (ref "SP1") (pin "3") (pinfunction "4.8V_3") (pintype "passive"))
    )
    (net (code "41") (name "Net-(D4-A)") (class "Default")
      (node (ref "D4") (pin "1") (pinfunction "A_1") (pintype "passive"))
      (node (ref "SP1") (pin "2") (pinfunction "3.6V_2") (pintype "passive"))
    )
    (net (code "42") (name "Net-(LED1-PadA)") (class "Default")
      (node (ref "LED1") (pin "A") (pintype "passive"))
      (node (ref "R21") (pin "2") (pinfunction "2_2") (pintype "passive"))
    )
    (net (code "43") (name "Net-(LED2-PadA)") (class "Default")
      (node (ref "LED2") (pin "A") (pintype "passive"))
      (node (ref "R22") (pin "2") (pinfunction "2_2") (pintype "passive"))
    )
    (net (code "44") (name "Net-(LED3-PadA)") (class "Default")
      (node (ref "LED3") (pin "A") (pintype "passive"))
      (node (ref "R29") (pin "2") (pinfunction "2_2") (pintype "passive"))
    )
    (net (code "45") (name "Net-(LED4-PadA)") (class "Default")
      (node (ref "LED4") (pin "A") (pintype "passive"))
      (node (ref "R32") (pin "2") (pinfunction "2_2") (pintype "passive"))
    )
    (net (code "46") (name "Net-(Q1-PadS)") (class "Default")
      (node (ref "Q1") (pin "S") (pinfunction "S_S") (pintype "passive"))
      (node (ref "R17") (pin "2") (pinfunction "2_2") (pintype "passive"))
    )
    (net (code "47") (name "Net-(Q2-D)") (class "Default")
      (node (ref "LED1") (pin "K") (pintype "passive"))
      (node (ref "Q2") (pin "3") (pinfunction "D_3") (pintype "passive"))
    )
    (net (code "48") (name "Net-(Q2-G)") (class "Default")
      (node (ref "Q2") (pin "1") (pinfunction "G_1") (pintype "passive"))
      (node (ref "R23") (pin "1") (pinfunction "1_1") (pintype "passive"))
      (node (ref "R25") (pin "2") (pinfunction "2_2") (pintype "passive"))
    )
    (net (code "49") (name "Net-(Q3-D)") (class "Default")
      (node (ref "LED2") (pin "K") (pintype "passive"))
      (node (ref "Q3") (pin "3") (pinfunction "D_3") (pintype "passive"))
    )
    (net (code "50") (name "Net-(Q3-G)") (class "Default")
      (node (ref "Q3") (pin "1") (pinfunction "G_1") (pintype "passive"))
      (node (ref "R24") (pin "1") (pinfunction "1_1") (pintype "passive"))
      (node (ref "R26") (pin "2") (pinfunction "2_2") (pintype "passive"))
    )
    (net (code "51") (name "Net-(Q4-D)") (class "Default")
      (node (ref "LED3") (pin "K") (pintype "passive"))
      (node (ref "Q4") (pin "3") (pinfunction "D_3") (pintype "passive"))
    )
    (net (code "52") (name "Net-(Q4-G)") (class "Default")
      (node (ref "Q4") (pin "1") (pinfunction "G_1") (pintype "passive"))
      (node (ref "R30") (pin "2") (pinfunction "2_2") (pintype "passive"))
      (node (ref "R31") (pin "1") (pinfunction "1_1") (pintype "passive"))
    )
    (net (code "53") (name "Net-(Q5-D)") (class "Default")
      (node (ref "LED4") (pin "K") (pintype "passive"))
      (node (ref "Q5") (pin "3") (pinfunction "D_3") (pintype "passive"))
    )
    (net (code "54") (name "Net-(Q5-G)") (class "Default")
      (node (ref "Q5") (pin "1") (pinfunction "G_1") (pintype "passive"))
      (node (ref "R33") (pin "2") (pinfunction "2_2") (pintype "passive"))
      (node (ref "R34") (pin "1") (pinfunction "1_1") (pintype "passive"))
    )
    (net (code "55") (name "Net-(Q6-G)") (class "Default")
      (node (ref "Q6") (pin "3") (pinfunction "G_3") (pintype "passive"))
      (node (ref "R47") (pin "1") (pinfunction "1_1") (pintype "passive"))
    )
    (net (code "56") (name "Net-(R10-Pad1)") (class "Default")
      (node (ref "R10") (pin "1") (pinfunction "1_1") (pintype "passive"))
      (node (ref "R4") (pin "1") (pinfunction "1_1") (pintype "passive"))
    )
    (net (code "57") (name "Net-(R18-Pad1)") (class "Default")
      (node (ref "R18") (pin "1") (pinfunction "1_1") (pintype "passive"))
      (node (ref "U5") (pin "2") (pinfunction "VOUT_2") (pintype "passive"))
      (node (ref "U5") (pin "3") (pinfunction "VOUT_3") (pintype "passive"))
    )
    (net (code "58") (name "Net-(R62-Pad1)") (class "Default")
      (node (ref "R62") (pin "1") (pinfunction "1_1") (pintype "passive"))
      (node (ref "U9") (pin "6") (pinfunction "6_6") (pintype "passive"))
    )
    (net (code "59") (name "Net-(R66-Pad2)") (class "Default")
      (node (ref "R66") (pin "2") (pinfunction "2_2") (pintype "passive"))
      (node (ref "R67") (pin "1") (pinfunction "1_1") (pintype "passive"))
      (node (ref "U8") (pin "6") (pinfunction "6_6") (pintype "passive"))
    )
    (net (code "60") (name "Net-(U1-FB)") (class "Default")
      (node (ref "C1") (pin "1") (pinfunction "1_1") (pintype "passive"))
      (node (ref "R1") (pin "1") (pinfunction "1_1") (pintype "passive"))
      (node (ref "R3") (pin "1") (pinfunction "1_1") (pintype "passive"))
      (node (ref "U1") (pin "5") (pinfunction "FB_5") (pintype "passive"))
    )
    (net (code "61") (name "Net-(U1-SW)") (class "Default")
      (node (ref "L1") (pin "B") (pinfunction "B_B") (pintype "passive"))
      (node (ref "U1") (pin "1") (pinfunction "SW_1") (pintype "passive"))
    )
    (net (code "62") (name "Net-(U2-LBST)") (class "Default")
      (node (ref "L2") (pin "B") (pinfunction "B_B") (pintype "passive"))
      (node (ref "U2") (pin "16") (pinfunction "LBST_16") (pintype "passive"))
    )
    (net (code "63") (name "Net-(U2-OK_HYST)") (class "Default")
      (node (ref "R5") (pin "1") (pinfunction "1_1") (pintype "passive"))
      (node (ref "R6") (pin "2") (pinfunction "2_2") (pintype "passive"))
      (node (ref "U2") (pin "9") (pinfunction "OK_HYST_9") (pintype "passive"))
    )
    (net (code "64") (name "Net-(U2-OK_PROG)") (class "Default")
      (node (ref "R6") (pin "1") (pinfunction "1_1") (pintype "passive"))
      (node (ref "R7") (pin "1") (pinfunction "1_1") (pintype "passive"))
      (node (ref "U2") (pin "10") (pinfunction "OK_PROG_10") (pintype "passive"))
    )
    (net (code "65") (name "Net-(U2-VBAT)") (class "Default")
      (node (ref "F3") (pin "2") (pinfunction "2_2") (pintype "passive"))
      (node (ref "U2") (pin "14") (pinfunction "VBAT_14") (pintype "passive"))
    )
    (net (code "66") (name "Net-(U2-VBAT_OK)") (class "Default")
      (node (ref "R20") (pin "2") (pinfunction "2_2") (pintype "passive"))
      (node (ref "U2") (pin "11") (pinfunction "VBAT_OK_11") (pintype "passive"))
    )
    (net (code "67") (name "Net-(U2-VBAT_OV)") (class "Default")
      (node (ref "R11") (pin "1") (pinfunction "1_1") (pintype "passive"))
      (node (ref "R8") (pin "2") (pinfunction "2_2") (pintype "passive"))
      (node (ref "U2") (pin "6") (pinfunction "VBAT_OV_6") (pintype "passive"))
    )
    (net (code "68") (name "Net-(U2-VBAT_UV)") (class "Default")
      (node (ref "R12") (pin "1") (pinfunction "1_1") (pintype "passive"))
      (node (ref "R9") (pin "1") (pinfunction "1_1") (pintype "passive"))
      (node (ref "U2") (pin "8") (pinfunction "VBAT_UV_8") (pintype "passive"))
    )
    (net (code "69") (name "Net-(U2-VOC_SAMP)") (class "Default")
      (node (ref "R2") (pin "1") (pinfunction "1_1") (pintype "passive"))
      (node (ref "R4") (pin "2") (pinfunction "2_2") (pintype "passive"))
      (node (ref "U2") (pin "3") (pinfunction "VOC_SAMP_3") (pintype "passive"))
    )
    (net (code "70") (name "Net-(U2-VRDIV)") (class "Default")
      (node (ref "R5") (pin "2") (pinfunction "2_2") (pintype "passive"))
      (node (ref "R8") (pin "1") (pinfunction "1_1") (pintype "passive"))
      (node (ref "R9") (pin "2") (pinfunction "2_2") (pintype "passive"))
      (node (ref "U2") (pin "7") (pinfunction "VRDIV_7") (pintype "passive"))
    )
    (net (code "71") (name "Net-(U2-VREF_SAMP)") (class "Default")
      (node (ref "C6") (pin "2") (pinfunction "2_2") (pintype "passive"))
      (node (ref "U2") (pin "4") (pinfunction "VREF_SAMP_4") (pintype "passive"))
    )
    (net (code "72") (name "Net-(U3-R1C1)") (class "Default")
      (node (ref "C7") (pin "2") (pinfunction "2_2") (pintype "passive"))
      (node (ref "R13") (pin "1") (pinfunction "1_1") (pintype "passive"))
      (node (ref "U3") (pin "6") (pinfunction "R1C1_6") (pintype "passive"))
    )
    (net (code "73") (name "Net-(U3-R2)") (class "Default")
      (node (ref "R19") (pin "1") (pinfunction "1_1") (pintype "passive"))
      (node (ref "U3") (pin "1") (pinfunction "R2_1") (pintype "passive"))
    )
    (net (code "74") (name "Net-(U5-ON{slash}~{OFF})") (class "Default")
      (node (ref "R15") (pin "2") (pinfunction "2_2") (pintype "passive"))
      (node (ref "U5") (pin "5") (pinfunction "ON/~{OFF}_5") (pintype "passive"))
    )
    (net (code "75") (name "Net-(U5-R1C1)") (class "Default")
      (node (ref "R16") (pin "1") (pinfunction "1_1") (pintype "passive"))
      (node (ref "U5") (pin "6") (pinfunction "R1C1_6") (pintype "passive"))
    )
    (net (code "76") (name "Net-(U6-PCTLZ)") (class "Default")
      (node (ref "Q1") (pin "G") (pinfunction "G_G") (pintype "passive"))
      (node (ref "TP6") (pin "1") (pinfunction "1_1") (pintype "passive"))
      (node (ref "U6") (pin "6") (pinfunction "PCTLZ_6") (pintype "passive"))
    )
    (net (code "77") (name "Net-(U8-NC)") (class "Default")
      (node (ref "R39") (pin "1") (pinfunction "1_1") (pintype "passive"))
      (node (ref "U8") (pin "3") (pinfunction "NC_3") (pintype "passive"))
    )
    (net (code "78") (name "Net-(U9-NC)") (class "Default")
      (node (ref "R60") (pin "1") (pinfunction "1_1") (pintype "passive"))
      (node (ref "U9") (pin "3") (pinfunction "NC_3") (pintype "passive"))
    )
    (net (code "79") (name "Net-(U10-EN)") (class "Default")
      (node (ref "C20") (pin "2") (pinfunction "2_2") (pintype "passive"))
      (node (ref "R58") (pin "2") (pinfunction "2_2") (pintype "passive"))
      (node (ref "U10") (pin "7") (pinfunction "VREF2_7") (pintype "passive"))
      (node (ref "U10") (pin "8") (pinfunction "EN_8") (pintype "passive"))
    )
    (net (code "80") (name "Net-(U10-SCL2)") (class "Default")
      (node (ref "R56") (pin "1") (pinfunction "1_1") (pintype "passive"))
      (node (ref "U10") (pin "6") (pinfunction "SCL2_6") (pintype "passive"))
      (node (ref "U6") (pin "4") (pinfunction "SCL_4") (pintype "passive"))
    )
    (net (code "81") (name "Net-(U10-SDA2)") (class "Default")
      (node (ref "R57") (pin "1") (pinfunction "1_1") (pintype "passive"))
      (node (ref "U10") (pin "5") (pinfunction "SDA2_5") (pintype "passive"))
      (node (ref "U6") (pin "5") (pinfunction "SDA_5") (pintype "passive"))
    )
    (net (code "82") (name "Net-(U11-CT)") (class "Default")
      (node (ref "C50") (pin "2") (pinfunction "2_2") (pintype "passive"))
      (node (ref "U11") (pin "4") (pinfunction "CT_4") (pintype "passive"))
    )
    (net (code "83") (name "Net-(U11-SENSE)") (class "Default")
      (node (ref "C52") (pin "1") (pinfunction "1_1") (pintype "passive"))
      (node (ref "C54") (pin "2") (pinfunction "2_2") (pintype "passive"))
      (node (ref "R64") (pin "2") (pinfunction "2_2") (pintype "passive"))
      (node (ref "R65") (pin "2") (pinfunction "2_2") (pintype "passive"))
      (node (ref "U11") (pin "5") (pinfunction "SENSE_5") (pintype "passive"))
    )
    (net (code "84") (name "Net-(U11-{slash}MR)") (class "Default")
      (node (ref "C9") (pin "2") (pinfunction "2_2") (pintype "passive"))
      (node (ref "P3") (pin "2") (pinfunction "2_2") (pintype "passive"))
      (node (ref "R63") (pin "2") (pinfunction "2_2") (pintype "passive"))
      (node (ref "SW1") (pin "2") (pinfunction "2_2") (pintype "passive"))
      (node (ref "U11") (pin "3") (pinfunction "/MR_3") (pintype "passive"))
    )
    (net (code "85") (name "VBAT_SENSE") (class "Default")
      (node (ref "P4") (pin "6") (pinfunction "DESIGNATOR=6_6") (pintype "passive"))
      (node (ref "R42") (pin "2") (pinfunction "2_2") (pintype "passive"))
      (node (ref "U9") (pin "5") (pinfunction "5_5") (pintype "passive"))
    )
    (net (code "86") (name "VBAT_SWITCHED") (class "Default")
      (node (ref "C4") (pin "2") (pinfunction "2_2") (pintype "passive"))
      (node (ref "C51") (pin "2") (pinfunction "2_2") (pintype "passive"))
      (node (ref "C52") (pin "2") (pinfunction "2_2") (pintype "passive"))
      (node (ref "C53") (pin "2") (pinfunction "2_2") (pintype "passive"))
      (node (ref "C7") (pin "1") (pinfunction "1_1") (pintype "passive"))
      (node (ref "C8") (pin "2") (pinfunction "2_2") (pintype "passive"))
      (node (ref "D11") (pin "2") (pinfunction "K_2") (pintype "passive"))
      (node (ref "D12") (pin "2") (pinfunction "K_2") (pintype "passive"))
      (node (ref "D13") (pin "2") (pinfunction "K_2") (pintype "passive"))
      (node (ref "D14") (pin "2") (pinfunction "K_2") (pintype "passive"))
      (node (ref "D16") (pin "2") (pinfunction "A_2") (pintype "passive"))
      (node (ref "L1") (pin "A") (pinfunction "A_A") (pintype "passive"))
      (node (ref "P6") (pin "4") (pintype "passive"))
      (node (ref "R35") (pin "1") (pinfunction "1_1") (pintype "passive"))
      (node (ref "R43") (pin "1") (pinfunction "1_1") (pintype "passive"))
      (node (ref "R55") (pin "2") (pinfunction "2_2") (pintype "passive"))
      (node (ref "R63") (pin "1") (pinfunction "1_1") (pintype "passive"))
      (node (ref "R64") (pin "1") (pinfunction "1_1") (pintype "passive"))
      (node (ref "R68") (pin "2") (pinfunction "2_2") (pintype "passive"))
      (node (ref "R69") (pin "1") (pinfunction "1_1") (pintype "passive"))
      (node (ref "RAD1") (pin "21") (pinfunction "VCC_21") (pintype "passive"))
      (node (ref "TP19") (pin "1") (pinfunction "1_1") (pintype "passive"))
      (node (ref "U1") (pin "3") (pinfunction "VIN_3") (pintype "passive"))
      (node (ref "U10") (pin "2") (pinfunction "VREF1_2") (pintype "passive"))
      (node (ref "U11") (pin "6") (pinfunction "VDD_6") (pintype "passive"))
      (node (ref "U3") (pin "2") (pinfunction "VOUT_2") (pintype "passive"))
      (node (ref "U3") (pin "3") (pinfunction "VOUT_3") (pintype "passive"))
    )
    (net (code "87") (name "unconnected-(D3-Pad3)") (class "Default")
      (node (ref "D3") (pin "3") (pinfunction "3_3") (pintype "passive+no_connect"))
    )
    (net (code "88") (name "unconnected-(MH1-Pad1)") (class "Default")
      (node (ref "MH1") (pin "1") (pinfunction "1_1") (pintype "passive"))
    )
    (net (code "89") (name "unconnected-(MH2-Pad1)") (class "Default")
      (node (ref "MH2") (pin "1") (pinfunction "1_1") (pintype "passive"))
    )
    (net (code "90") (name "unconnected-(P6-Pad11)") (class "Default")
      (node (ref "P6") (pin "11") (pintype "passive"))
    )
    (net (code "91") (name "unconnected-(RAD1-GPIO12{slash}ADC1{slash}PF1-Pad14)") (class "Default")
      (node (ref "RAD1") (pin "14") (pinfunction "GPIO12/ADC1/PF1_14") (pintype "passive"))
    )
    (net (code "92") (name "unconnected-(U9-NO-Pad1)") (class "Default")
      (node (ref "U9") (pin "1") (pinfunction "NO_1") (pintype "passive"))
    )
  )
)
